# fc-comms.net
KiCad netlist of a schematic drawn in EAGLE
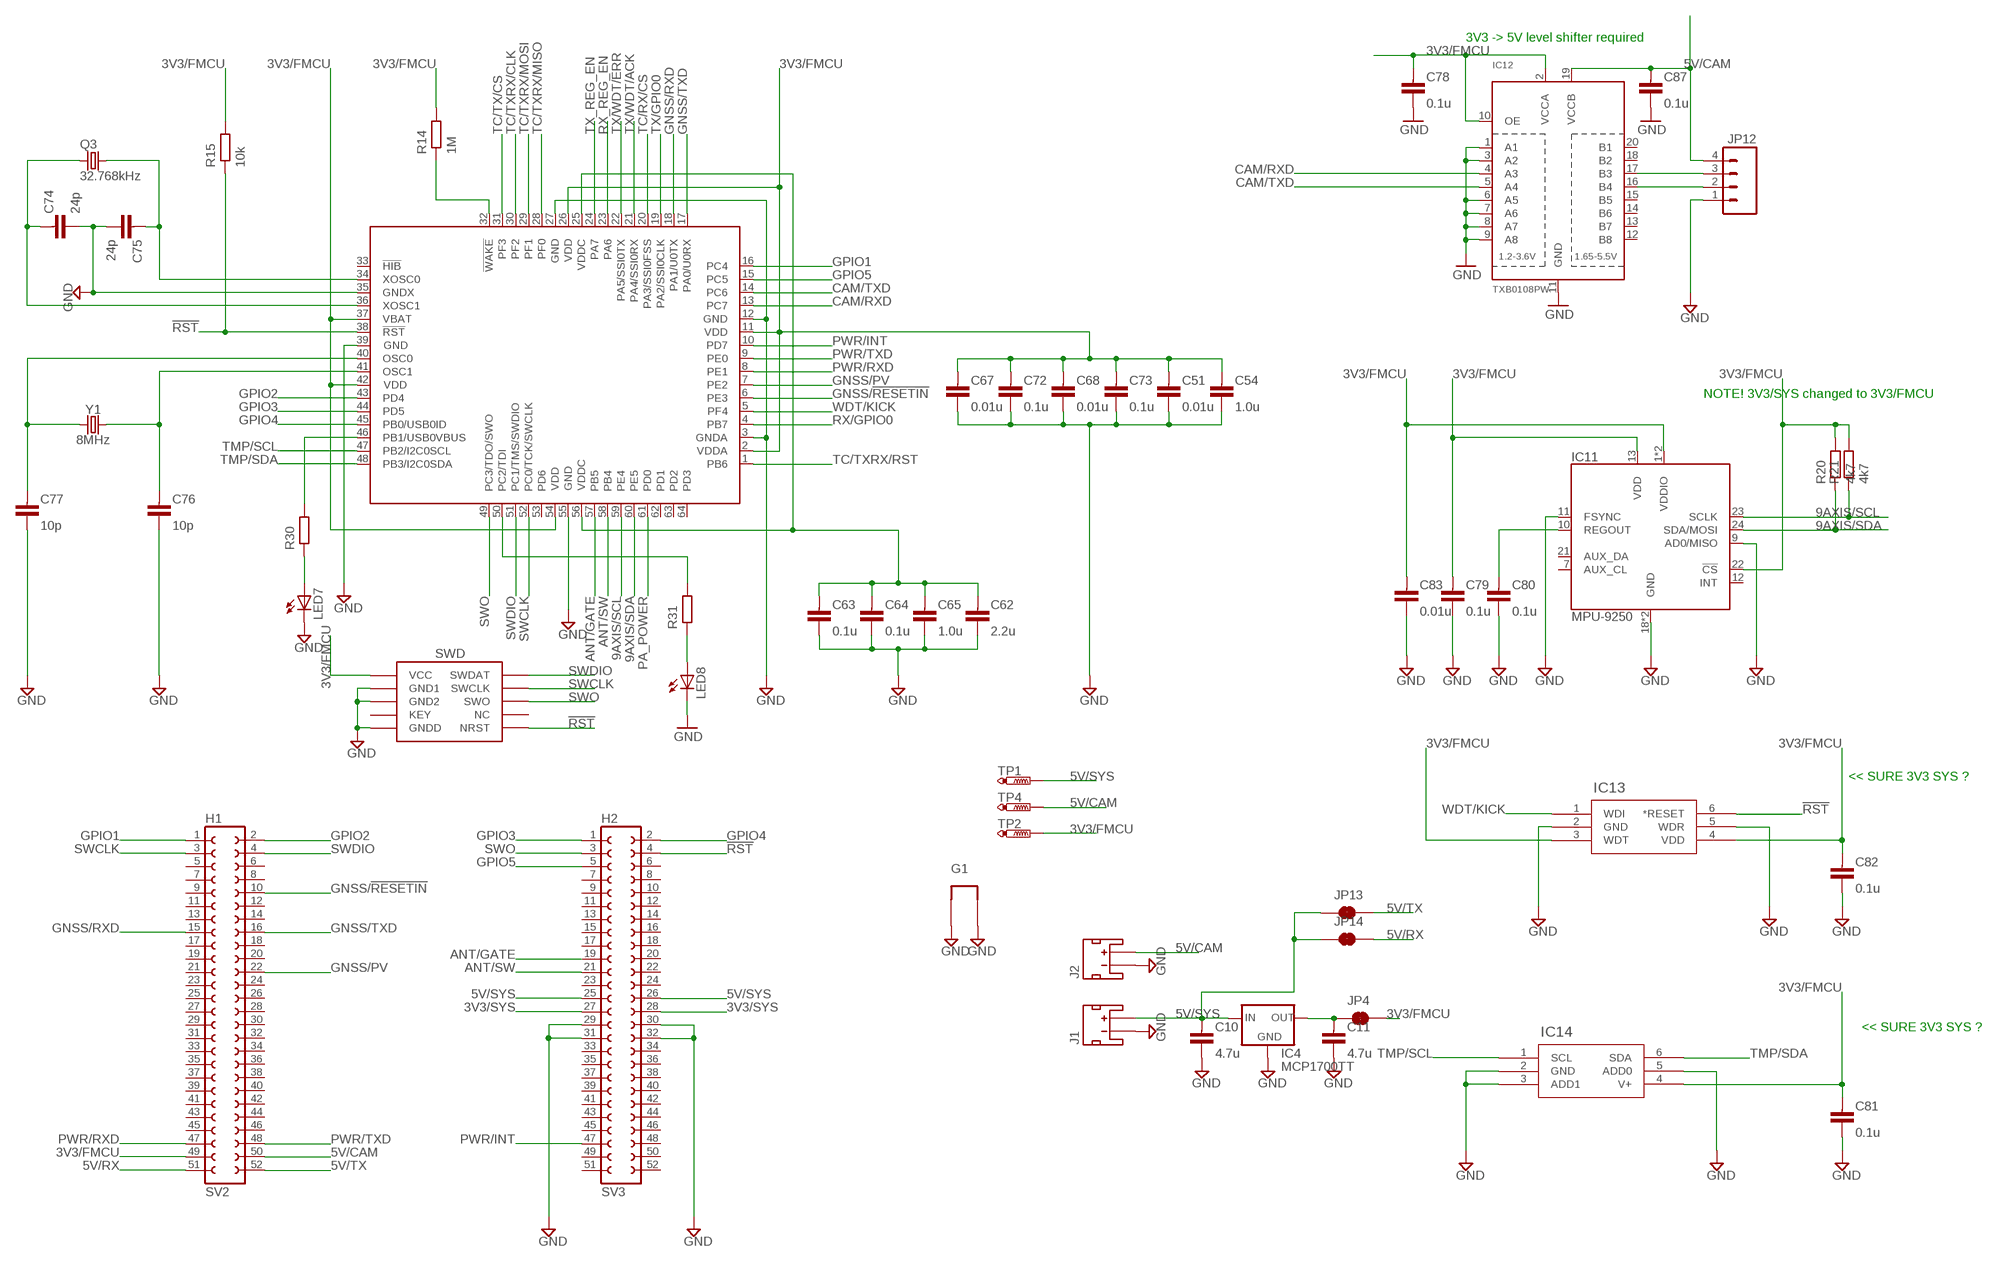
[diagram p0: schematic, sheet 1]
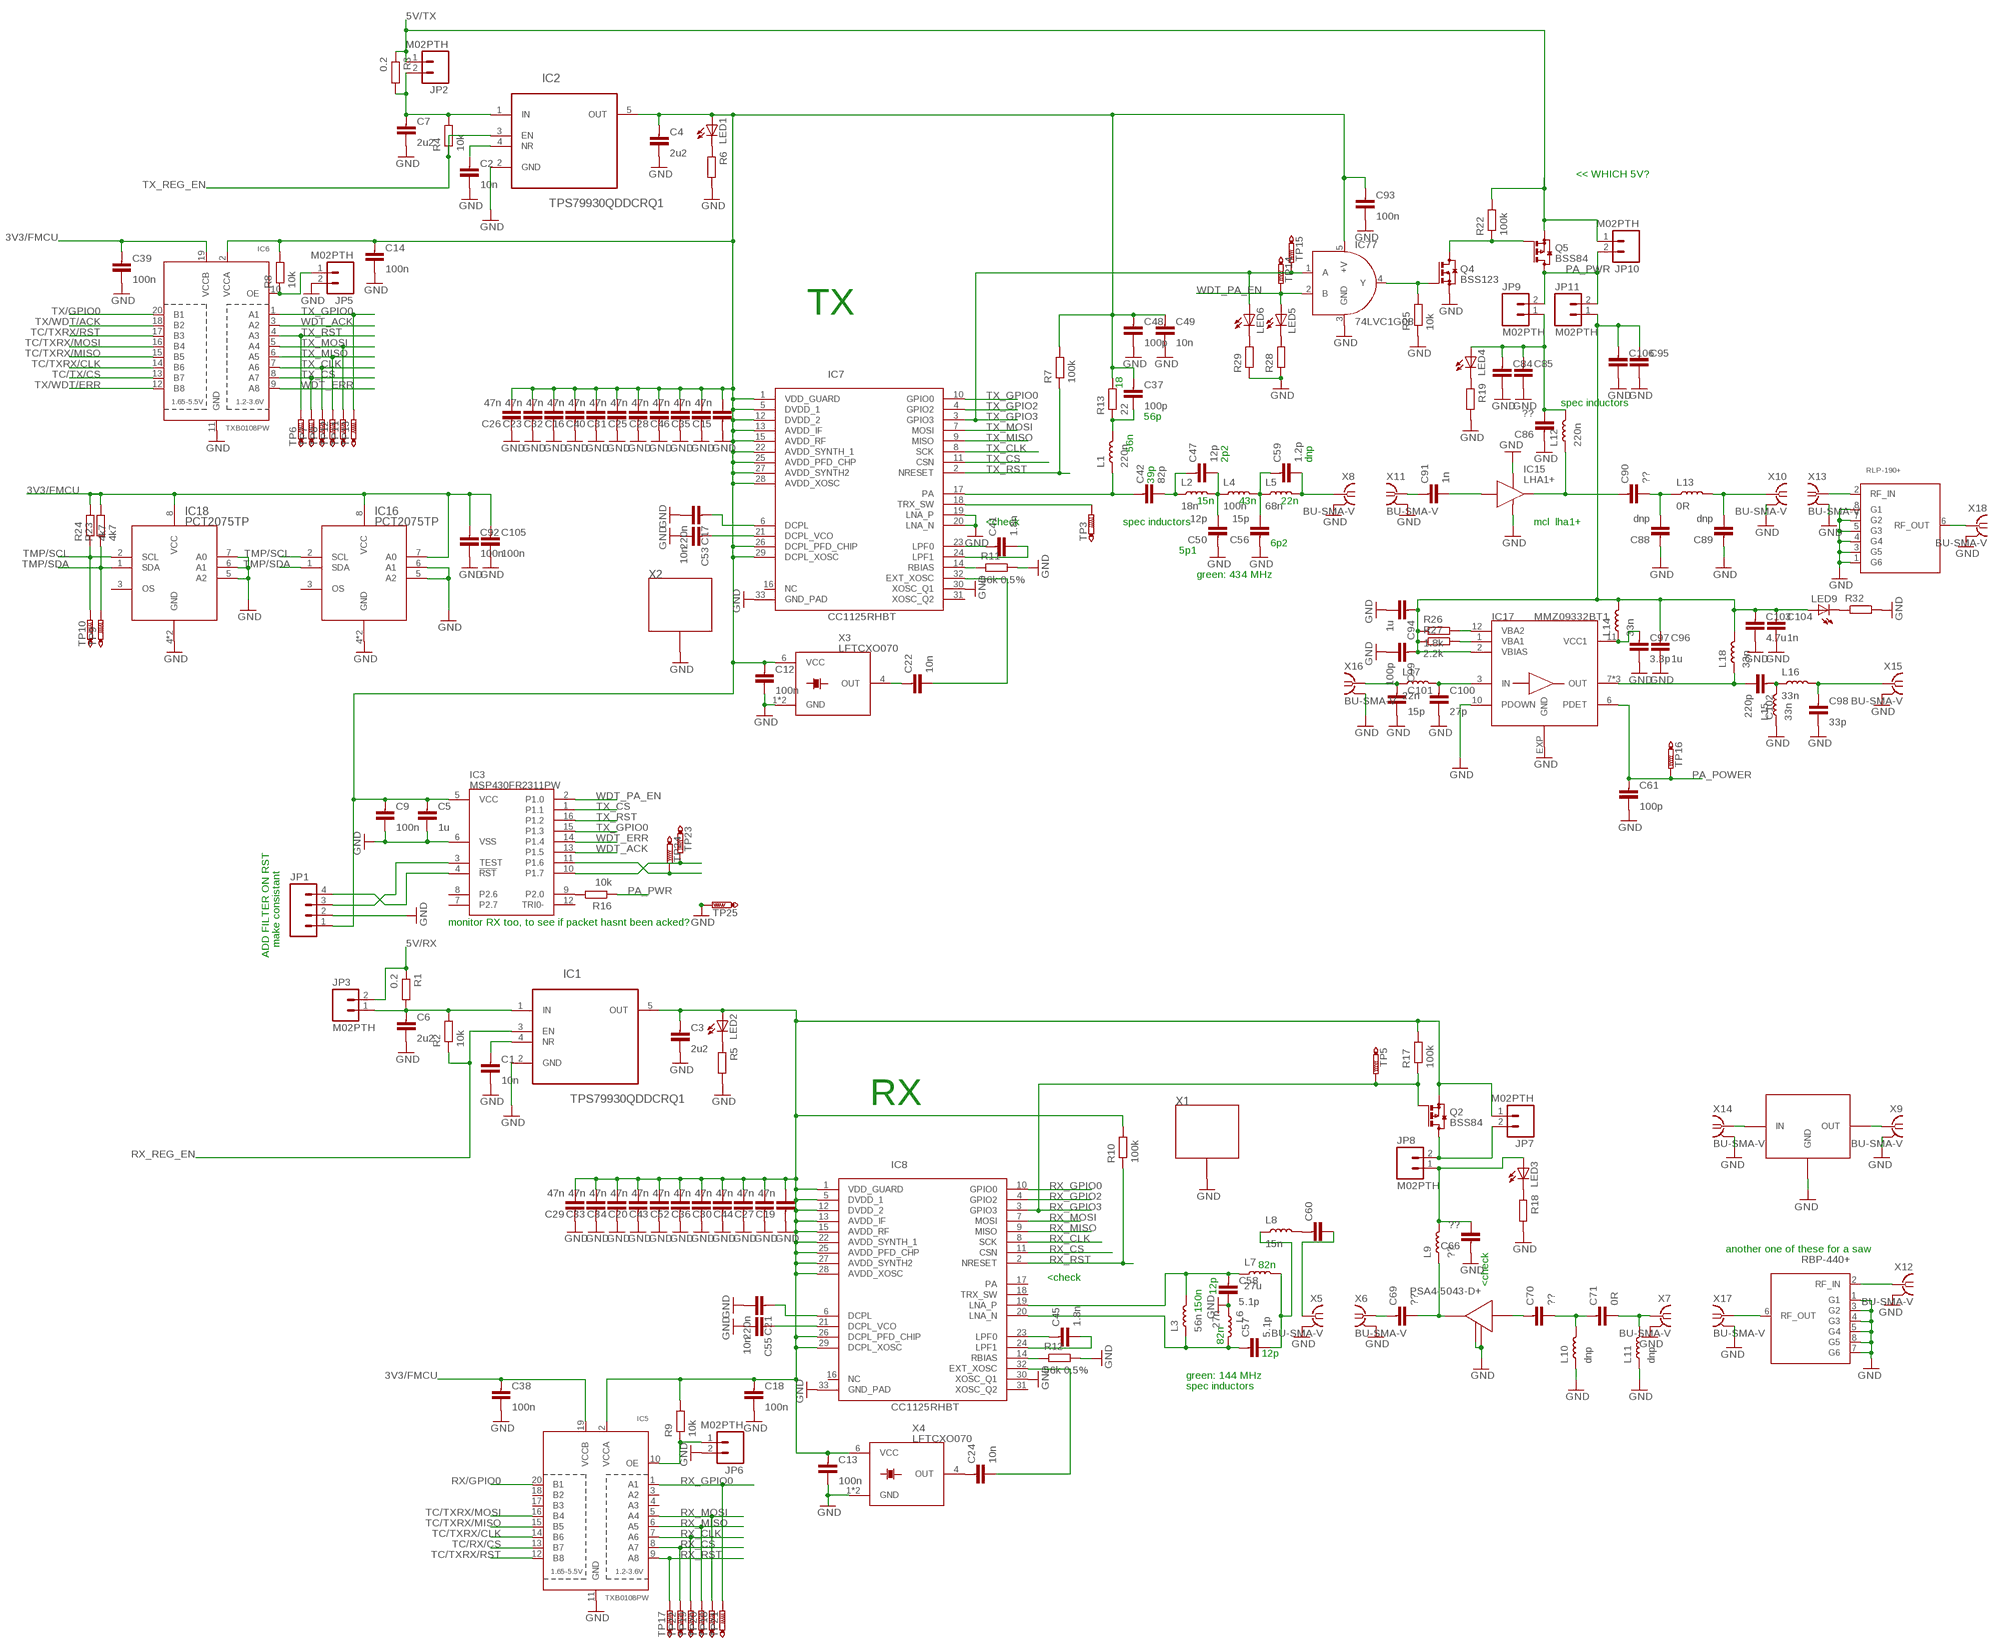
[diagram p1: schematic, sheet 2]

(export (version "E")
  (design (tool "Eeschema 10.0.6"))
  (components
    (comp (ref "C10")
      (value "4.7u")
      (footprint "eagle-import:C0603-N")
      (libsource (lib "eagle-import") (part "CAPACITOR0603-N"))
    )
    (comp (ref "C11")
      (value "4.7u")
      (footprint "eagle-import:C0603-N")
      (libsource (lib "eagle-import") (part "CAPACITOR0603-N"))
    )
    (comp (ref "C51")
      (value "0.01u")
      (footprint "eagle-import:C0603-N")
      (libsource (lib "eagle-import") (part "CAPACITOR0603-N"))
    )
    (comp (ref "C54")
      (value "1.0u")
      (footprint "eagle-import:C0603-N")
      (libsource (lib "eagle-import") (part "CAPACITOR0603-N"))
    )
    (comp (ref "C62")
      (value "2.2u")
      (footprint "eagle-import:C0603-N")
      (libsource (lib "eagle-import") (part "CAPACITOR0603-N"))
    )
    (comp (ref "C63")
      (value "0.1u")
      (footprint "eagle-import:C0603-N")
      (libsource (lib "eagle-import") (part "CAPACITOR0603-N"))
    )
    (comp (ref "C64")
      (value "0.1u")
      (footprint "eagle-import:C0603-N")
      (libsource (lib "eagle-import") (part "CAPACITOR0603-N"))
    )
    (comp (ref "C65")
      (value "1.0u")
      (footprint "eagle-import:C0603-N")
      (libsource (lib "eagle-import") (part "CAPACITOR0603-N"))
    )
    (comp (ref "C67")
      (value "0.01u")
      (footprint "eagle-import:C0603-N")
      (libsource (lib "eagle-import") (part "CAPACITOR0603-N"))
    )
    (comp (ref "C68")
      (value "0.01u")
      (footprint "eagle-import:C0603-N")
      (libsource (lib "eagle-import") (part "CAPACITOR0603-N"))
    )
    (comp (ref "C72")
      (value "0.1u")
      (footprint "eagle-import:C0603-N")
      (libsource (lib "eagle-import") (part "CAPACITOR0603-N"))
    )
    (comp (ref "C73")
      (value "0.1u")
      (footprint "eagle-import:C0603-N")
      (libsource (lib "eagle-import") (part "CAPACITOR0603-N"))
    )
    (comp (ref "C74")
      (value "24p")
      (footprint "eagle-import:C0603-N")
      (libsource (lib "eagle-import") (part "CAPACITOR0603-N"))
    )
    (comp (ref "C75")
      (value "24p")
      (footprint "eagle-import:C0603-N")
      (libsource (lib "eagle-import") (part "CAPACITOR0603-N"))
    )
    (comp (ref "C76")
      (value "10p")
      (footprint "eagle-import:C0603-N")
      (libsource (lib "eagle-import") (part "CAPACITOR0603-N"))
    )
    (comp (ref "C77")
      (value "10p")
      (footprint "eagle-import:C0603-N")
      (libsource (lib "eagle-import") (part "CAPACITOR0603-N"))
    )
    (comp (ref "C78")
      (value "0.1u")
      (footprint "eagle-import:C0603-N")
      (libsource (lib "eagle-import") (part "CAPACITOR0603-N"))
    )
    (comp (ref "C79")
      (value "0.1u")
      (footprint "eagle-import:C0603-N")
      (libsource (lib "eagle-import") (part "CAPACITOR0603-N"))
    )
    (comp (ref "C80")
      (value "0.1u")
      (footprint "eagle-import:C0603-N")
      (libsource (lib "eagle-import") (part "CAPACITOR0603-N"))
    )
    (comp (ref "C81")
      (value "0.1u")
      (footprint "eagle-import:C0603-N")
      (libsource (lib "eagle-import") (part "CAPACITOR0603-N"))
    )
    (comp (ref "C82")
      (value "0.1u")
      (footprint "eagle-import:C0603-N")
      (libsource (lib "eagle-import") (part "CAPACITOR0603-N"))
    )
    (comp (ref "C83")
      (value "0.01u")
      (footprint "eagle-import:C0603-N")
      (libsource (lib "eagle-import") (part "CAPACITOR0603-N"))
    )
    (comp (ref "C87")
      (value "0.1u")
      (footprint "eagle-import:C0603-N")
      (libsource (lib "eagle-import") (part "CAPACITOR0603-N"))
    )
    (comp (ref "G1")
      (value "GND-LOOPL")
      (footprint "eagle-import:GND-LOOP-0.4")
      (libsource (lib "eagle-import") (part "GND-LOOPL"))
    )
    (comp (ref "IC4")
      (value "MCP1700TT")
      (footprint "eagle-import:SOT23")
      (libsource (lib "eagle-import") (part "MCP1700TT"))
    )
    (comp (ref "IC9")
      (value "TM4C123[7,G]XXPM")
      (footprint "eagle-import:PM_S-PQFP-G64")
      (libsource (lib "eagle-import") (part "TM4C123[7,G]XXPM"))
    )
    (comp (ref "IC11")
      (value "MPU-9250")
      (footprint "eagle-import:QFN-24_3MM")
      (libsource (lib "eagle-import") (part "MPU-9250"))
    )
    (comp (ref "IC12")
      (value "TXB0108PW")
      (footprint "eagle-import:TSSOP20")
      (libsource (lib "eagle-import") (part "TXB0108PW"))
    )
    (comp (ref "IC13")
      (value "TPS3813K33-EP_DBV_6")
      (footprint "eagle-import:DBV6")
      (fields
        (field (name "GENERIC_PART_NUMBER") "TPS3813K33-EP")
        (field (name "MANUFACTURER") "Texas Instruments")
        (field (name "MANUFACTURER_PART_NUMBER") "tps3813k33-ep_dbv_6")
      )
      (libsource (lib "eagle-import") (part "TPS3813K33-EP_DBV_6"))
    )
    (comp (ref "IC14")
      (value "TMP100-EP_DBV_6")
      (footprint "eagle-import:DBV6")
      (fields
        (field (name "GENERIC_PART_NUMBER") "TMP100-EP")
        (field (name "MANUFACTURER") "Texas Instruments")
        (field (name "MANUFACTURER_PART_NUMBER") "tmp100-ep_dbv_6")
      )
      (libsource (lib "eagle-import") (part "TMP100-EP_DBV_6"))
    )
    (comp (ref "J1")
      (value "JST_2MM_MALE_TH")
      (footprint "eagle-import:JST-2-TH")
      (libsource (lib "eagle-import") (part "JST_2MM_MALE_TH"))
    )
    (comp (ref "J2")
      (value "JST_2MM_MALE_TH")
      (footprint "eagle-import:JST-2-TH")
      (libsource (lib "eagle-import") (part "JST_2MM_MALE_TH"))
    )
    (comp (ref "J3")
      (value "SWD_SHROUD")
      (footprint "eagle-import:SWD_PTH_SHROUD")
      (libsource (lib "eagle-import") (part "SWD_SHROUD"))
    )
    (comp (ref "JP4")
      (value "JUMPER-SMT_2_NC_TRACE_SILK")
      (footprint "eagle-import:SMT-JUMPER_2_NC_TRACE_SILK")
      (libsource (lib "eagle-import") (part "JUMPER-SMT_2_NC_TRACE_SILK"))
    )
    (comp (ref "JP12")
      (value "M04PTH")
      (footprint "eagle-import:1X04")
      (libsource (lib "eagle-import") (part "M04PTH"))
    )
    (comp (ref "JP13")
      (value "JUMPER-SMT_2_NC_TRACE_SILK")
      (footprint "eagle-import:SMT-JUMPER_2_NC_TRACE_SILK")
      (libsource (lib "eagle-import") (part "JUMPER-SMT_2_NC_TRACE_SILK"))
    )
    (comp (ref "JP14")
      (value "JUMPER-SMT_2_NC_TRACE_SILK")
      (footprint "eagle-import:SMT-JUMPER_2_NC_TRACE_SILK")
      (libsource (lib "eagle-import") (part "JUMPER-SMT_2_NC_TRACE_SILK"))
    )
    (comp (ref "LED7")
      (value "LEDCHIP-LED0603")
      (footprint "eagle-import:CHIP-LED0603")
      (libsource (lib "eagle-import") (part "LEDCHIP-LED0603"))
    )
    (comp (ref "LED8")
      (value "LEDCHIP-LED0603")
      (footprint "eagle-import:CHIP-LED0603")
      (libsource (lib "eagle-import") (part "LEDCHIP-LED0603"))
    )
    (comp (ref "Q3")
      (value "32.768kHz")
      (footprint "eagle-import:RESONATOR_EPSON_FC_145")
      (libsource (lib "eagle-import") (part "RESONATOR_EPSON_FC_145"))
    )
    (comp (ref "R14")
      (value "1M")
      (footprint "eagle-import:R0603-N")
      (libsource (lib "eagle-import") (part "RESISTOR0603-N"))
    )
    (comp (ref "R15")
      (value "10k")
      (footprint "eagle-import:R0603-N")
      (libsource (lib "eagle-import") (part "RESISTOR0603-N"))
    )
    (comp (ref "R20")
      (value "4k7")
      (footprint "eagle-import:R0603-N")
      (libsource (lib "eagle-import") (part "RESISTOR0603-N"))
    )
    (comp (ref "R21")
      (value "4k7")
      (footprint "eagle-import:R0603-N")
      (libsource (lib "eagle-import") (part "RESISTOR0603-N"))
    )
    (comp (ref "R30")
      (value "RESISTOR0603-N")
      (footprint "eagle-import:R0603-N")
      (libsource (lib "eagle-import") (part "RESISTOR0603-N"))
    )
    (comp (ref "R31")
      (value "RESISTOR0603-N")
      (footprint "eagle-import:R0603-N")
      (libsource (lib "eagle-import") (part "RESISTOR0603-N"))
    )
    (comp (ref "SV2")
      (value "H1")
      (footprint "eagle-import:FE26-2")
      (libsource (lib "eagle-import") (part "FE26-2"))
    )
    (comp (ref "SV3")
      (value "H2")
      (footprint "eagle-import:FE26-2")
      (libsource (lib "eagle-import") (part "FE26-2"))
    )
    (comp (ref "TP1")
      (value "PTR1PAD1-13")
      (footprint "eagle-import:P1-13")
      (libsource (lib "eagle-import") (part "PTR1PAD1-13"))
    )
    (comp (ref "TP2")
      (value "PTR1PAD1-13")
      (footprint "eagle-import:P1-13")
      (libsource (lib "eagle-import") (part "PTR1PAD1-13"))
    )
    (comp (ref "TP4")
      (value "PTR1PAD1-13")
      (footprint "eagle-import:P1-13")
      (libsource (lib "eagle-import") (part "PTR1PAD1-13"))
    )
    (comp (ref "Y1")
      (value "8MHz")
      (footprint "eagle-import:CRYSTAL-SMD-5X3.2-4PAD")
      (libsource (lib "eagle-import") (part "CRYSTAL-8MHZSMD-5X3.2"))
    )
    (comp (ref "C1")
      (value "10n")
      (footprint "eagle-import:C0603-N")
      (libsource (lib "eagle-import") (part "CAPACITOR0603-N"))
    )
    (comp (ref "C2")
      (value "10n")
      (footprint "eagle-import:C0603-N")
      (libsource (lib "eagle-import") (part "CAPACITOR0603-N"))
    )
    (comp (ref "C3")
      (value "2u2")
      (footprint "eagle-import:C0603-N")
      (libsource (lib "eagle-import") (part "CAPACITOR0603-N"))
    )
    (comp (ref "C4")
      (value "2u2")
      (footprint "eagle-import:C0603-N")
      (libsource (lib "eagle-import") (part "CAPACITOR0603-N"))
    )
    (comp (ref "C5")
      (value "1u")
      (footprint "eagle-import:C0603-N")
      (libsource (lib "eagle-import") (part "CAPACITOR0603-N"))
    )
    (comp (ref "C6")
      (value "2u2")
      (footprint "eagle-import:C0603-N")
      (libsource (lib "eagle-import") (part "CAPACITOR0603-N"))
    )
    (comp (ref "C7")
      (value "2u2")
      (footprint "eagle-import:C0603-N")
      (libsource (lib "eagle-import") (part "CAPACITOR0603-N"))
    )
    (comp (ref "C9")
      (value "100n")
      (footprint "eagle-import:C0603-N")
      (libsource (lib "eagle-import") (part "CAPACITOR0603-N"))
    )
    (comp (ref "C12")
      (value "100n")
      (footprint "eagle-import:C0603-N")
      (libsource (lib "eagle-import") (part "CAPACITOR0603-N"))
    )
    (comp (ref "C13")
      (value "100n")
      (footprint "eagle-import:C0603-N")
      (libsource (lib "eagle-import") (part "CAPACITOR0603-N"))
    )
    (comp (ref "C14")
      (value "100n")
      (footprint "eagle-import:C0603-N")
      (libsource (lib "eagle-import") (part "CAPACITOR0603-N"))
    )
    (comp (ref "C15")
      (value "47n")
      (footprint "eagle-import:C0603-N")
      (libsource (lib "eagle-import") (part "CAPACITOR0603-N"))
    )
    (comp (ref "C16")
      (value "47n")
      (footprint "eagle-import:C0603-N")
      (libsource (lib "eagle-import") (part "CAPACITOR0603-N"))
    )
    (comp (ref "C17")
      (value "220n")
      (footprint "eagle-import:C0603-N")
      (libsource (lib "eagle-import") (part "CAPACITOR0603-N"))
    )
    (comp (ref "C18")
      (value "100n")
      (footprint "eagle-import:C0603-N")
      (libsource (lib "eagle-import") (part "CAPACITOR0603-N"))
    )
    (comp (ref "C19")
      (value "47n")
      (footprint "eagle-import:C0603-N")
      (libsource (lib "eagle-import") (part "CAPACITOR0603-N"))
    )
    (comp (ref "C20")
      (value "47n")
      (footprint "eagle-import:C0603-N")
      (libsource (lib "eagle-import") (part "CAPACITOR0603-N"))
    )
    (comp (ref "C21")
      (value "220n")
      (footprint "eagle-import:C0603-N")
      (libsource (lib "eagle-import") (part "CAPACITOR0603-N"))
    )
    (comp (ref "C22")
      (value "10n")
      (footprint "eagle-import:C0603-N")
      (libsource (lib "eagle-import") (part "CAPACITOR0603-N"))
    )
    (comp (ref "C23")
      (value "47n")
      (footprint "eagle-import:C0603-N")
      (libsource (lib "eagle-import") (part "CAPACITOR0603-N"))
    )
    (comp (ref "C24")
      (value "10n")
      (footprint "eagle-import:C0603-N")
      (libsource (lib "eagle-import") (part "CAPACITOR0603-N"))
    )
    (comp (ref "C25")
      (value "47n")
      (footprint "eagle-import:C0603-N")
      (libsource (lib "eagle-import") (part "CAPACITOR0603-N"))
    )
    (comp (ref "C26")
      (value "47n")
      (footprint "eagle-import:C0603-N")
      (libsource (lib "eagle-import") (part "CAPACITOR0603-N"))
    )
    (comp (ref "C27")
      (value "47n")
      (footprint "eagle-import:C0603-N")
      (libsource (lib "eagle-import") (part "CAPACITOR0603-N"))
    )
    (comp (ref "C28")
      (value "47n")
      (footprint "eagle-import:C0603-N")
      (libsource (lib "eagle-import") (part "CAPACITOR0603-N"))
    )
    (comp (ref "C29")
      (value "47n")
      (footprint "eagle-import:C0603-N")
      (libsource (lib "eagle-import") (part "CAPACITOR0603-N"))
    )
    (comp (ref "C30")
      (value "47n")
      (footprint "eagle-import:C0603-N")
      (libsource (lib "eagle-import") (part "CAPACITOR0603-N"))
    )
    (comp (ref "C31")
      (value "47n")
      (footprint "eagle-import:C0603-N")
      (libsource (lib "eagle-import") (part "CAPACITOR0603-N"))
    )
    (comp (ref "C32")
      (value "47n")
      (footprint "eagle-import:C0603-N")
      (libsource (lib "eagle-import") (part "CAPACITOR0603-N"))
    )
    (comp (ref "C33")
      (value "47n")
      (footprint "eagle-import:C0603-N")
      (libsource (lib "eagle-import") (part "CAPACITOR0603-N"))
    )
    (comp (ref "C34")
      (value "47n")
      (footprint "eagle-import:C0603-N")
      (libsource (lib "eagle-import") (part "CAPACITOR0603-N"))
    )
    (comp (ref "C35")
      (value "47n")
      (footprint "eagle-import:C0603-N")
      (libsource (lib "eagle-import") (part "CAPACITOR0603-N"))
    )
    (comp (ref "C36")
      (value "47n")
      (footprint "eagle-import:C0603-N")
      (libsource (lib "eagle-import") (part "CAPACITOR0603-N"))
    )
    (comp (ref "C37")
      (value "100p")
      (footprint "eagle-import:C0603-N")
      (libsource (lib "eagle-import") (part "CAPACITOR0603-N"))
    )
    (comp (ref "C38")
      (value "100n")
      (footprint "eagle-import:C0603-N")
      (libsource (lib "eagle-import") (part "CAPACITOR0603-N"))
    )
    (comp (ref "C39")
      (value "100n")
      (footprint "eagle-import:C0603-N")
      (libsource (lib "eagle-import") (part "CAPACITOR0603-N"))
    )
    (comp (ref "C40")
      (value "47n")
      (footprint "eagle-import:C0603-N")
      (libsource (lib "eagle-import") (part "CAPACITOR0603-N"))
    )
    (comp (ref "C41")
      (value "1.8n")
      (footprint "eagle-import:C0603-N")
      (libsource (lib "eagle-import") (part "CAPACITOR0603-N"))
    )
    (comp (ref "C42")
      (value "82p")
      (footprint "eagle-import:C0603-N")
      (libsource (lib "eagle-import") (part "CAPACITOR0603-N"))
    )
    (comp (ref "C43")
      (value "47n")
      (footprint "eagle-import:C0603-N")
      (libsource (lib "eagle-import") (part "CAPACITOR0603-N"))
    )
    (comp (ref "C44")
      (value "47n")
      (footprint "eagle-import:C0603-N")
      (libsource (lib "eagle-import") (part "CAPACITOR0603-N"))
    )
    (comp (ref "C45")
      (value "1.8n")
      (footprint "eagle-import:C0603-N")
      (libsource (lib "eagle-import") (part "CAPACITOR0603-N"))
    )
    (comp (ref "C46")
      (value "47n")
      (footprint "eagle-import:C0603-N")
      (libsource (lib "eagle-import") (part "CAPACITOR0603-N"))
    )
    (comp (ref "C47")
      (value "12p")
      (footprint "eagle-import:C0603-N")
      (libsource (lib "eagle-import") (part "CAPACITOR0603-N"))
    )
    (comp (ref "C48")
      (value "100p")
      (footprint "eagle-import:C0603-N")
      (libsource (lib "eagle-import") (part "CAPACITOR0603-N"))
    )
    (comp (ref "C49")
      (value "10n")
      (footprint "eagle-import:C0603-N")
      (libsource (lib "eagle-import") (part "CAPACITOR0603-N"))
    )
    (comp (ref "C50")
      (value "12p")
      (footprint "eagle-import:C0603-N")
      (libsource (lib "eagle-import") (part "CAPACITOR0603-N"))
    )
    (comp (ref "C52")
      (value "47n")
      (footprint "eagle-import:C0603-N")
      (libsource (lib "eagle-import") (part "CAPACITOR0603-N"))
    )
    (comp (ref "C53")
      (value "10n")
      (footprint "eagle-import:C0603-N")
      (libsource (lib "eagle-import") (part "CAPACITOR0603-N"))
    )
    (comp (ref "C55")
      (value "10n")
      (footprint "eagle-import:C0603-N")
      (libsource (lib "eagle-import") (part "CAPACITOR0603-N"))
    )
    (comp (ref "C56")
      (value "15p")
      (footprint "eagle-import:C0603-N")
      (libsource (lib "eagle-import") (part "CAPACITOR0603-N"))
    )
    (comp (ref "C57")
      (value "5.1p")
      (footprint "eagle-import:C0603-N")
      (libsource (lib "eagle-import") (part "CAPACITOR0603-N"))
    )
    (comp (ref "C58")
      (value "5.1p")
      (footprint "eagle-import:C0603-N")
      (libsource (lib "eagle-import") (part "CAPACITOR0603-N"))
    )
    (comp (ref "C59")
      (value "1.2p")
      (footprint "eagle-import:C0603-N")
      (libsource (lib "eagle-import") (part "CAPACITOR0603-N"))
    )
    (comp (ref "C60")
      (value "CAPACITOR0603-N")
      (footprint "eagle-import:C0603-N")
      (libsource (lib "eagle-import") (part "CAPACITOR0603-N"))
    )
    (comp (ref "C61")
      (value "100p")
      (footprint "eagle-import:C0603-N")
      (libsource (lib "eagle-import") (part "CAPACITOR0603-N"))
    )
    (comp (ref "C66")
      (value "??")
      (footprint "eagle-import:C0603-N")
      (libsource (lib "eagle-import") (part "CAPACITOR0603-N"))
    )
    (comp (ref "C69")
      (value "??")
      (footprint "eagle-import:C0603-N")
      (libsource (lib "eagle-import") (part "CAPACITOR0603-N"))
    )
    (comp (ref "C70")
      (value "??")
      (footprint "eagle-import:C0603-N")
      (libsource (lib "eagle-import") (part "CAPACITOR0603-N"))
    )
    (comp (ref "C71")
      (value "0R")
      (footprint "eagle-import:C0603-N")
      (libsource (lib "eagle-import") (part "CAPACITOR0603-N"))
    )
    (comp (ref "C84")
      (value "CAPACITOR0805-N")
      (footprint "eagle-import:C0805-N")
      (libsource (lib "eagle-import") (part "CAPACITOR0805-N"))
    )
    (comp (ref "C85")
      (value "CAPACITOR0805-N")
      (footprint "eagle-import:C0805-N")
      (libsource (lib "eagle-import") (part "CAPACITOR0805-N"))
    )
    (comp (ref "C86")
      (value "??")
      (footprint "eagle-import:C0603-N")
      (libsource (lib "eagle-import") (part "CAPACITOR0603-N"))
    )
    (comp (ref "C88")
      (value "dnp")
      (footprint "eagle-import:C0603-N")
      (libsource (lib "eagle-import") (part "CAPACITOR0603-N"))
    )
    (comp (ref "C89")
      (value "dnp")
      (footprint "eagle-import:C0603-N")
      (libsource (lib "eagle-import") (part "CAPACITOR0603-N"))
    )
    (comp (ref "C90")
      (value "??")
      (footprint "eagle-import:C0603-N")
      (libsource (lib "eagle-import") (part "CAPACITOR0603-N"))
    )
    (comp (ref "C91")
      (value "1n")
      (footprint "eagle-import:C0603-N")
      (libsource (lib "eagle-import") (part "CAPACITOR0603-N"))
    )
    (comp (ref "C92")
      (value "100n")
      (footprint "eagle-import:C0603-N")
      (libsource (lib "eagle-import") (part "CAPACITOR0603-N"))
    )
    (comp (ref "C93")
      (value "100n")
      (footprint "eagle-import:C0603-N")
      (libsource (lib "eagle-import") (part "CAPACITOR0603-N"))
    )
    (comp (ref "C94")
      (value "1u")
      (footprint "eagle-import:C0603-N")
      (libsource (lib "eagle-import") (part "CAPACITOR0603-N"))
    )
    (comp (ref "C95")
      (value "CAPACITOR0805-N")
      (footprint "eagle-import:C0805-N")
      (libsource (lib "eagle-import") (part "CAPACITOR0805-N"))
    )
    (comp (ref "C96")
      (value "1u")
      (footprint "eagle-import:C0603-N")
      (libsource (lib "eagle-import") (part "CAPACITOR0603-N"))
    )
    (comp (ref "C97")
      (value "3.3p")
      (footprint "eagle-import:C0603-N")
      (libsource (lib "eagle-import") (part "CAPACITOR0603-N"))
    )
    (comp (ref "C98")
      (value "33p")
      (footprint "eagle-import:C0603-N")
      (libsource (lib "eagle-import") (part "CAPACITOR0603-N"))
    )
    (comp (ref "C99")
      (value "100p")
      (footprint "eagle-import:C0603-N")
      (libsource (lib "eagle-import") (part "CAPACITOR0603-N"))
    )
    (comp (ref "C100")
      (value "27p")
      (footprint "eagle-import:C0603-N")
      (libsource (lib "eagle-import") (part "CAPACITOR0603-N"))
    )
    (comp (ref "C101")
      (value "15p")
      (footprint "eagle-import:C0603-N")
      (libsource (lib "eagle-import") (part "CAPACITOR0603-N"))
    )
    (comp (ref "C102")
      (value "220p")
      (footprint "eagle-import:C0603-N")
      (libsource (lib "eagle-import") (part "CAPACITOR0603-N"))
    )
    (comp (ref "C103")
      (value "4.7u")
      (footprint "eagle-import:C0603-N")
      (libsource (lib "eagle-import") (part "CAPACITOR0603-N"))
    )
    (comp (ref "C104")
      (value "1n")
      (footprint "eagle-import:C0603-N")
      (libsource (lib "eagle-import") (part "CAPACITOR0603-N"))
    )
    (comp (ref "C105")
      (value "100n")
      (footprint "eagle-import:C0603-N")
      (libsource (lib "eagle-import") (part "CAPACITOR0603-N"))
    )
    (comp (ref "C106")
      (value "CAPACITOR0805-N")
      (footprint "eagle-import:C0805-N")
      (libsource (lib "eagle-import") (part "CAPACITOR0805-N"))
    )
    (comp (ref "FL1")
      (value "GOLLEDGE_SAW_FILTER")
      (footprint "eagle-import:GOLLEDGE_SAW")
      (libsource (lib "eagle-import") (part "GOLLEDGE_SAW_FILTER"))
    )
    (comp (ref "FL2")
      (value "SAW_FILTER_CS")
      (footprint "eagle-import:PL-176")
      (libsource (lib "eagle-import") (part "SAW_FILTER_CS"))
    )
    (comp (ref "FL3")
      (value "LPF_CS")
      (footprint "eagle-import:PL-176")
      (libsource (lib "eagle-import") (part "LPF_CS"))
    )
    (comp (ref "IC1")
      (value "TPS79930QDDCRQ1")
      (footprint "eagle-import:SOT95P280X110-5N")
      (fields (field (name "MPN") "TPS79933QDDCRQ1"))
      (libsource (lib "eagle-import") (part "TPS79933QDDCRQ1"))
    )
    (comp (ref "IC2")
      (value "TPS79930QDDCRQ1")
      (footprint "eagle-import:SOT95P280X110-5N")
      (fields (field (name "MPN") "TPS79933QDDCRQ1"))
      (libsource (lib "eagle-import") (part "TPS79933QDDCRQ1"))
    )
    (comp (ref "IC3")
      (value "MSP430FR2311PW")
      (footprint "eagle-import:SSOP16")
      (libsource (lib "eagle-import") (part "MSP430FR2311PW"))
    )
    (comp (ref "IC5")
      (value "TXB0108PW")
      (footprint "eagle-import:TSSOP20")
      (libsource (lib "eagle-import") (part "TXB0108PW"))
    )
    (comp (ref "IC6")
      (value "TXB0108PW")
      (footprint "eagle-import:TSSOP20")
      (libsource (lib "eagle-import") (part "TXB0108PW"))
    )
    (comp (ref "IC7")
      (value "CC1125RHBT")
      (footprint "eagle-import:QFN32_5X5")
      (libsource (lib "eagle-import") (part "CC1125RHBT"))
    )
    (comp (ref "IC8")
      (value "CC1125RHBT")
      (footprint "eagle-import:QFN32_5X5")
      (libsource (lib "eagle-import") (part "CC1125RHBT"))
    )
    (comp (ref "IC10")
      (value "LNA_COMMON")
      (footprint "eagle-import:LNA_MMM1362")
      (libsource (lib "eagle-import") (part "LNA_COMMON"))
    )
    (comp (ref "IC15")
      (value "LHA1+")
      (footprint "eagle-import:PA")
      (libsource (lib "eagle-import") (part "PA"))
    )
    (comp (ref "IC16")
      (value "PCT2075TP")
      (footprint "eagle-import:HWSON8")
      (libsource (lib "eagle-import") (part "PCT2075TP"))
    )
    (comp (ref "IC17")
      (value "MMZ09332BT1")
      (footprint "eagle-import:QFN3X3-6")
      (libsource (lib "eagle-import") (part "MMZ09332BT1"))
    )
    (comp (ref "IC18")
      (value "PCT2075TP")
      (footprint "eagle-import:HWSON8")
      (libsource (lib "eagle-import") (part "PCT2075TP"))
    )
    (comp (ref "IC77")
      (value "74LVC1G08")
      (footprint "eagle-import:SOT23-5")
      (libsource (lib "eagle-import") (part "SN74LVC1G08"))
    )
    (comp (ref "JP1")
      (value "M04PTH")
      (footprint "eagle-import:1X04")
      (libsource (lib "eagle-import") (part "M04PTH"))
    )
    (comp (ref "JP2")
      (value "M02PTH")
      (footprint "eagle-import:1X02")
      (libsource (lib "eagle-import") (part "M02PTH"))
    )
    (comp (ref "JP3")
      (value "M02PTH")
      (footprint "eagle-import:1X02")
      (libsource (lib "eagle-import") (part "M02PTH"))
    )
    (comp (ref "JP5")
      (value "M02PTH")
      (footprint "eagle-import:1X02")
      (libsource (lib "eagle-import") (part "M02PTH"))
    )
    (comp (ref "JP6")
      (value "M02PTH")
      (footprint "eagle-import:1X02")
      (libsource (lib "eagle-import") (part "M02PTH"))
    )
    (comp (ref "JP7")
      (value "M02PTH")
      (footprint "eagle-import:1X02")
      (libsource (lib "eagle-import") (part "M02PTH"))
    )
    (comp (ref "JP8")
      (value "M02PTH")
      (footprint "eagle-import:1X02")
      (libsource (lib "eagle-import") (part "M02PTH"))
    )
    (comp (ref "JP9")
      (value "M02PTH")
      (footprint "eagle-import:1X02")
      (libsource (lib "eagle-import") (part "M02PTH"))
    )
    (comp (ref "JP10")
      (value "M02PTH")
      (footprint "eagle-import:1X02")
      (libsource (lib "eagle-import") (part "M02PTH"))
    )
    (comp (ref "JP11")
      (value "M02PTH")
      (footprint "eagle-import:1X02")
      (libsource (lib "eagle-import") (part "M02PTH"))
    )
    (comp (ref "L1")
      (value "220n")
      (footprint "eagle-import:L0603-N")
      (libsource (lib "eagle-import") (part "INDUCTOR0603-N"))
    )
    (comp (ref "L2")
      (value "18n")
      (footprint "eagle-import:L0603-N")
      (libsource (lib "eagle-import") (part "INDUCTOR0603-N"))
    )
    (comp (ref "L3")
      (value "56n")
      (footprint "eagle-import:L0603-N")
      (libsource (lib "eagle-import") (part "INDUCTOR0603-N"))
    )
    (comp (ref "L4")
      (value "100n")
      (footprint "eagle-import:L0603-N")
      (libsource (lib "eagle-import") (part "INDUCTOR0603-N"))
    )
    (comp (ref "L5")
      (value "68n")
      (footprint "eagle-import:L0603-N")
      (libsource (lib "eagle-import") (part "INDUCTOR0603-N"))
    )
    (comp (ref "L6")
      (value "27n")
      (footprint "eagle-import:L0603-N")
      (libsource (lib "eagle-import") (part "INDUCTOR0603-N"))
    )
    (comp (ref "L7")
      (value "27u")
      (footprint "eagle-import:L0603-N")
      (libsource (lib "eagle-import") (part "INDUCTOR0603-N"))
    )
    (comp (ref "L8")
      (value "15n")
      (footprint "eagle-import:L0603-N")
      (libsource (lib "eagle-import") (part "INDUCTOR0603-N"))
    )
    (comp (ref "L9")
      (value "??")
      (footprint "eagle-import:L0603-N")
      (libsource (lib "eagle-import") (part "INDUCTOR0603-N"))
    )
    (comp (ref "L10")
      (value "dnp")
      (footprint "eagle-import:L0603-N")
      (libsource (lib "eagle-import") (part "INDUCTOR0603-N"))
    )
    (comp (ref "L11")
      (value "dnp")
      (footprint "eagle-import:L0603-N")
      (libsource (lib "eagle-import") (part "INDUCTOR0603-N"))
    )
    (comp (ref "L12")
      (value "220n")
      (footprint "eagle-import:L0603-N")
      (libsource (lib "eagle-import") (part "INDUCTOR0603-N"))
    )
    (comp (ref "L13")
      (value "0R")
      (footprint "eagle-import:L0603-N")
      (libsource (lib "eagle-import") (part "INDUCTOR0603-N"))
    )
    (comp (ref "L14")
      (value "33n")
      (footprint "eagle-import:L0603-N")
      (libsource (lib "eagle-import") (part "INDUCTOR0603-N"))
    )
    (comp (ref "L15")
      (value "33n")
      (footprint "eagle-import:L0603-N")
      (libsource (lib "eagle-import") (part "INDUCTOR0603-N"))
    )
    (comp (ref "L16")
      (value "33n")
      (footprint "eagle-import:L0603-N")
      (libsource (lib "eagle-import") (part "INDUCTOR0603-N"))
    )
    (comp (ref "L17")
      (value "22n")
      (footprint "eagle-import:L0603-N")
      (libsource (lib "eagle-import") (part "INDUCTOR0603-N"))
    )
    (comp (ref "L18")
      (value "33n")
      (footprint "eagle-import:L0603-N")
      (libsource (lib "eagle-import") (part "INDUCTOR0603-N"))
    )
    (comp (ref "LED1")
      (value "LEDCHIP-LED0603")
      (footprint "eagle-import:CHIP-LED0603")
      (libsource (lib "eagle-import") (part "LEDCHIP-LED0603"))
    )
    (comp (ref "LED2")
      (value "LEDCHIP-LED0603")
      (footprint "eagle-import:CHIP-LED0603")
      (libsource (lib "eagle-import") (part "LEDCHIP-LED0603"))
    )
    (comp (ref "LED3")
      (value "LEDCHIP-LED0603")
      (footprint "eagle-import:CHIP-LED0603")
      (libsource (lib "eagle-import") (part "LEDCHIP-LED0603"))
    )
    (comp (ref "LED4")
      (value "LEDCHIP-LED0603")
      (footprint "eagle-import:CHIP-LED0603")
      (libsource (lib "eagle-import") (part "LEDCHIP-LED0603"))
    )
    (comp (ref "LED5")
      (value "LEDCHIP-LED0603")
      (footprint "eagle-import:CHIP-LED0603")
      (libsource (lib "eagle-import") (part "LEDCHIP-LED0603"))
    )
    (comp (ref "LED6")
      (value "LEDCHIP-LED0603")
      (footprint "eagle-import:CHIP-LED0603")
      (libsource (lib "eagle-import") (part "LEDCHIP-LED0603"))
    )
    (comp (ref "LED9")
      (value "LEDCHIP-LED0603")
      (footprint "eagle-import:CHIP-LED0603")
      (libsource (lib "eagle-import") (part "LEDCHIP-LED0603"))
    )
    (comp (ref "Q2")
      (value "BSS84")
      (footprint "eagle-import:SOT23")
      (libsource (lib "eagle-import") (part "BSS84"))
    )
    (comp (ref "Q4")
      (value "BSS123")
      (footprint "eagle-import:SOT23")
      (libsource (lib "eagle-import") (part "BSS123"))
    )
    (comp (ref "Q5")
      (value "BSS84")
      (footprint "eagle-import:SOT23")
      (libsource (lib "eagle-import") (part "BSS84"))
    )
    (comp (ref "R1")
      (value "0.2")
      (footprint "eagle-import:R0603-N")
      (libsource (lib "eagle-import") (part "RESISTOR0603-N"))
    )
    (comp (ref "R2")
      (value "10k")
      (footprint "eagle-import:R0603-N")
      (libsource (lib "eagle-import") (part "RESISTOR0603-N"))
    )
    (comp (ref "R3")
      (value "0.2")
      (footprint "eagle-import:R0603-N")
      (libsource (lib "eagle-import") (part "RESISTOR0603-N"))
    )
    (comp (ref "R4")
      (value "10k")
      (footprint "eagle-import:R0603-N")
      (libsource (lib "eagle-import") (part "RESISTOR0603-N"))
    )
    (comp (ref "R5")
      (value "RESISTOR0603-N")
      (footprint "eagle-import:R0603-N")
      (libsource (lib "eagle-import") (part "RESISTOR0603-N"))
    )
    (comp (ref "R6")
      (value "RESISTOR0603-N")
      (footprint "eagle-import:R0603-N")
      (libsource (lib "eagle-import") (part "RESISTOR0603-N"))
    )
    (comp (ref "R7")
      (value "100k")
      (footprint "eagle-import:R0603-N")
      (libsource (lib "eagle-import") (part "RESISTOR0603-N"))
    )
    (comp (ref "R8")
      (value "10k")
      (footprint "eagle-import:R0603-N")
      (libsource (lib "eagle-import") (part "RESISTOR0603-N"))
    )
    (comp (ref "R9")
      (value "10k")
      (footprint "eagle-import:R0603-N")
      (libsource (lib "eagle-import") (part "RESISTOR0603-N"))
    )
    (comp (ref "R10")
      (value "100k")
      (footprint "eagle-import:R0603-N")
      (libsource (lib "eagle-import") (part "RESISTOR0603-N"))
    )
    (comp (ref "R11")
      (value "56k 0.5%")
      (footprint "eagle-import:R0603-N")
      (libsource (lib "eagle-import") (part "RESISTOR0603-N"))
    )
    (comp (ref "R12")
      (value "56k 0.5%")
      (footprint "eagle-import:R0603-N")
      (libsource (lib "eagle-import") (part "RESISTOR0603-N"))
    )
    (comp (ref "R13")
      (value "22")
      (footprint "eagle-import:R0603-N")
      (libsource (lib "eagle-import") (part "RESISTOR0603-N"))
    )
    (comp (ref "R16")
      (value "10k")
      (footprint "eagle-import:R0603-N")
      (libsource (lib "eagle-import") (part "RESISTOR0603-N"))
    )
    (comp (ref "R17")
      (value "100k")
      (footprint "eagle-import:R0603-N")
      (libsource (lib "eagle-import") (part "RESISTOR0603-N"))
    )
    (comp (ref "R18")
      (value "RESISTOR0603-N")
      (footprint "eagle-import:R0603-N")
      (libsource (lib "eagle-import") (part "RESISTOR0603-N"))
    )
    (comp (ref "R19")
      (value "RESISTOR0603-N")
      (footprint "eagle-import:R0603-N")
      (libsource (lib "eagle-import") (part "RESISTOR0603-N"))
    )
    (comp (ref "R22")
      (value "100k")
      (footprint "eagle-import:R0603-N")
      (libsource (lib "eagle-import") (part "RESISTOR0603-N"))
    )
    (comp (ref "R23")
      (value "4k7")
      (footprint "eagle-import:R0603-N")
      (libsource (lib "eagle-import") (part "RESISTOR0603-N"))
    )
    (comp (ref "R24")
      (value "4k7")
      (footprint "eagle-import:R0603-N")
      (libsource (lib "eagle-import") (part "RESISTOR0603-N"))
    )
    (comp (ref "R25")
      (value "10k")
      (footprint "eagle-import:R0603-N")
      (libsource (lib "eagle-import") (part "RESISTOR0603-N"))
    )
    (comp (ref "R26")
      (value "1.8k")
      (footprint "eagle-import:R0603-N")
      (libsource (lib "eagle-import") (part "RESISTOR0603-N"))
    )
    (comp (ref "R27")
      (value "2.2k")
      (footprint "eagle-import:R0603-N")
      (libsource (lib "eagle-import") (part "RESISTOR0603-N"))
    )
    (comp (ref "R28")
      (value "RESISTOR0603-N")
      (footprint "eagle-import:R0603-N")
      (libsource (lib "eagle-import") (part "RESISTOR0603-N"))
    )
    (comp (ref "R29")
      (value "RESISTOR0603-N")
      (footprint "eagle-import:R0603-N")
      (libsource (lib "eagle-import") (part "RESISTOR0603-N"))
    )
    (comp (ref "R32")
      (value "RESISTOR0603-N")
      (footprint "eagle-import:R0603-N")
      (libsource (lib "eagle-import") (part "RESISTOR0603-N"))
    )
    (comp (ref "TP3")
      (value "PTR1B1,27")
      (footprint "eagle-import:B1,27")
      (libsource (lib "eagle-import") (part "PTR1B1,27"))
    )
    (comp (ref "TP5")
      (value "PTR1B1,27")
      (footprint "eagle-import:B1,27")
      (libsource (lib "eagle-import") (part "PTR1B1,27"))
    )
    (comp (ref "TP6")
      (value "PTR1B1,27")
      (footprint "eagle-import:B1,27")
      (libsource (lib "eagle-import") (part "PTR1B1,27"))
    )
    (comp (ref "TP7")
      (value "PTR1B1,27")
      (footprint "eagle-import:B1,27")
      (libsource (lib "eagle-import") (part "PTR1B1,27"))
    )
    (comp (ref "TP8")
      (value "PTR1B1,27")
      (footprint "eagle-import:B1,27")
      (libsource (lib "eagle-import") (part "PTR1B1,27"))
    )
    (comp (ref "TP9")
      (value "PTR1B1,27")
      (footprint "eagle-import:B1,27")
      (libsource (lib "eagle-import") (part "PTR1B1,27"))
    )
    (comp (ref "TP10")
      (value "PTR1B1,27")
      (footprint "eagle-import:B1,27")
      (libsource (lib "eagle-import") (part "PTR1B1,27"))
    )
    (comp (ref "TP11")
      (value "PTR1B1,27")
      (footprint "eagle-import:B1,27")
      (libsource (lib "eagle-import") (part "PTR1B1,27"))
    )
    (comp (ref "TP12")
      (value "PTR1B1,27")
      (footprint "eagle-import:B1,27")
      (libsource (lib "eagle-import") (part "PTR1B1,27"))
    )
    (comp (ref "TP13")
      (value "PTR1B1,27")
      (footprint "eagle-import:B1,27")
      (libsource (lib "eagle-import") (part "PTR1B1,27"))
    )
    (comp (ref "TP14")
      (value "PTR1B1,27")
      (footprint "eagle-import:B1,27")
      (libsource (lib "eagle-import") (part "PTR1B1,27"))
    )
    (comp (ref "TP15")
      (value "PTR1B1,27")
      (footprint "eagle-import:B1,27")
      (libsource (lib "eagle-import") (part "PTR1B1,27"))
    )
    (comp (ref "TP16")
      (value "PTR1B1,27")
      (footprint "eagle-import:B1,27")
      (libsource (lib "eagle-import") (part "PTR1B1,27"))
    )
    (comp (ref "TP17")
      (value "PTR1B1,27")
      (footprint "eagle-import:B1,27")
      (libsource (lib "eagle-import") (part "PTR1B1,27"))
    )
    (comp (ref "TP18")
      (value "PTR1B1,27")
      (footprint "eagle-import:B1,27")
      (libsource (lib "eagle-import") (part "PTR1B1,27"))
    )
    (comp (ref "TP19")
      (value "PTR1B1,27")
      (footprint "eagle-import:B1,27")
      (libsource (lib "eagle-import") (part "PTR1B1,27"))
    )
    (comp (ref "TP20")
      (value "PTR1B1,27")
      (footprint "eagle-import:B1,27")
      (libsource (lib "eagle-import") (part "PTR1B1,27"))
    )
    (comp (ref "TP21")
      (value "PTR1B1,27")
      (footprint "eagle-import:B1,27")
      (libsource (lib "eagle-import") (part "PTR1B1,27"))
    )
    (comp (ref "TP22")
      (value "PTR1B1,27")
      (footprint "eagle-import:B1,27")
      (libsource (lib "eagle-import") (part "PTR1B1,27"))
    )
    (comp (ref "TP23")
      (value "PTR1B1,27")
      (footprint "eagle-import:B1,27")
      (libsource (lib "eagle-import") (part "PTR1B1,27"))
    )
    (comp (ref "TP24")
      (value "PTR1B1,27")
      (footprint "eagle-import:B1,27")
      (libsource (lib "eagle-import") (part "PTR1B1,27"))
    )
    (comp (ref "TP25")
      (value "PTR1B1,27")
      (footprint "eagle-import:B1,27")
      (libsource (lib "eagle-import") (part "PTR1B1,27"))
    )
    (comp (ref "X1")
      (value "SHIELD-26X26")
      (footprint "eagle-import:SHIELD-26X26")
      (libsource (lib "eagle-import") (part "SHIELD-26X26"))
    )
    (comp (ref "X2")
      (value "SHIELD-26X26")
      (footprint "eagle-import:SHIELD-26X26")
      (libsource (lib "eagle-import") (part "SHIELD-26X26"))
    )
    (comp (ref "X3")
      (value "LFTCXO070")
      (footprint "eagle-import:260-SERIES")
      (libsource (lib "eagle-import") (part "LFTCXO070"))
    )
    (comp (ref "X4")
      (value "LFTCXO070")
      (footprint "eagle-import:260-SERIES")
      (libsource (lib "eagle-import") (part "LFTCXO070"))
    )
    (comp (ref "X5")
      (value "BU-SMA-V")
      (footprint "eagle-import:BU-SMA-V")
      (libsource (lib "eagle-import") (part "BU-SMA-V"))
    )
    (comp (ref "X6")
      (value "BU-SMA-V")
      (footprint "eagle-import:BU-SMA-V")
      (libsource (lib "eagle-import") (part "BU-SMA-V"))
    )
    (comp (ref "X7")
      (value "BU-SMA-V")
      (footprint "eagle-import:BU-SMA-V")
      (libsource (lib "eagle-import") (part "BU-SMA-V"))
    )
    (comp (ref "X8")
      (value "BU-SMA-V")
      (footprint "eagle-import:BU-SMA-V")
      (libsource (lib "eagle-import") (part "BU-SMA-V"))
    )
    (comp (ref "X9")
      (value "BU-SMA-V")
      (footprint "eagle-import:BU-SMA-V")
      (libsource (lib "eagle-import") (part "BU-SMA-V"))
    )
    (comp (ref "X10")
      (value "BU-SMA-V")
      (footprint "eagle-import:BU-SMA-V")
      (libsource (lib "eagle-import") (part "BU-SMA-V"))
    )
    (comp (ref "X11")
      (value "BU-SMA-V")
      (footprint "eagle-import:BU-SMA-V")
      (libsource (lib "eagle-import") (part "BU-SMA-V"))
    )
    (comp (ref "X12")
      (value "BU-SMA-V")
      (footprint "eagle-import:BU-SMA-V")
      (libsource (lib "eagle-import") (part "BU-SMA-V"))
    )
    (comp (ref "X13")
      (value "BU-SMA-V")
      (footprint "eagle-import:BU-SMA-V")
      (libsource (lib "eagle-import") (part "BU-SMA-V"))
    )
    (comp (ref "X14")
      (value "BU-SMA-V")
      (footprint "eagle-import:BU-SMA-V")
      (libsource (lib "eagle-import") (part "BU-SMA-V"))
    )
    (comp (ref "X15")
      (value "BU-SMA-V")
      (footprint "eagle-import:BU-SMA-V")
      (libsource (lib "eagle-import") (part "BU-SMA-V"))
    )
    (comp (ref "X16")
      (value "BU-SMA-V")
      (footprint "eagle-import:BU-SMA-V")
      (libsource (lib "eagle-import") (part "BU-SMA-V"))
    )
    (comp (ref "X17")
      (value "BU-SMA-V")
      (footprint "eagle-import:BU-SMA-V")
      (libsource (lib "eagle-import") (part "BU-SMA-V"))
    )
    (comp (ref "X18")
      (value "BU-SMA-V")
      (footprint "eagle-import:BU-SMA-V")
      (libsource (lib "eagle-import") (part "BU-SMA-V"))
    )
  )
  (nets
    (net (code "1") (name "3V3{slash}FMCU") (class "Default")
      (node (ref "C105") (pin "1") (pinfunction "1_1") (pintype "passive"))
      (node (ref "C38") (pin "1") (pinfunction "1_1") (pintype "passive"))
      (node (ref "C39") (pin "1") (pinfunction "1_1") (pintype "passive"))
      (node (ref "C51") (pin "1") (pinfunction "1_1") (pintype "passive"))
      (node (ref "C54") (pin "1") (pinfunction "1_1") (pintype "passive"))
      (node (ref "C67") (pin "1") (pinfunction "1_1") (pintype "passive"))
      (node (ref "C68") (pin "1") (pinfunction "1_1") (pintype "passive"))
      (node (ref "C72") (pin "1") (pinfunction "1_1") (pintype "passive"))
      (node (ref "C73") (pin "1") (pinfunction "1_1") (pintype "passive"))
      (node (ref "C78") (pin "1") (pinfunction "1_1") (pintype "passive"))
      (node (ref "C79") (pin "1") (pinfunction "1_1") (pintype "passive"))
      (node (ref "C81") (pin "1") (pinfunction "1_1") (pintype "passive"))
      (node (ref "C82") (pin "1") (pinfunction "1_1") (pintype "passive"))
      (node (ref "C83") (pin "1") (pinfunction "1_1") (pintype "passive"))
      (node (ref "C92") (pin "1") (pinfunction "1_1") (pintype "passive"))
      (node (ref "IC11") (pin "1") (pinfunction "VDDIO_1") (pintype "bidirectional"))
      (node (ref "IC11") (pin "13") (pinfunction "VDD_13") (pintype "bidirectional"))
      (node (ref "IC11") (pin "22") (pinfunction "~{CS}_22") (pintype "bidirectional"))
      (node (ref "IC11") (pin "8") (pinfunction "VDDIO_8") (pintype "bidirectional"))
      (node (ref "IC12") (pin "10") (pinfunction "OE_10") (pintype "bidirectional"))
      (node (ref "IC12") (pin "2") (pinfunction "VCCA_2") (pintype "bidirectional"))
      (node (ref "IC13") (pin "3") (pinfunction "WDT_3") (pintype "input"))
      (node (ref "IC13") (pin "4") (pinfunction "VDD_4") (pintype "input"))
      (node (ref "IC14") (pin "4") (pinfunction "V+_4") (pintype "power_in"))
      (node (ref "IC16") (pin "7") (pinfunction "A0_7") (pintype "input"))
      (node (ref "IC16") (pin "8") (pinfunction "VCC_8") (pintype "power_in"))
      (node (ref "IC18") (pin "8") (pinfunction "VCC_8") (pintype "power_in"))
      (node (ref "IC5") (pin "19") (pinfunction "VCCB_19") (pintype "bidirectional"))
      (node (ref "IC6") (pin "19") (pinfunction "VCCB_19") (pintype "bidirectional"))
      (node (ref "IC9") (pin "11") (pinfunction "VDD_11") (pintype "bidirectional"))
      (node (ref "IC9") (pin "2") (pinfunction "VDDA_2") (pintype "bidirectional"))
      (node (ref "IC9") (pin "26") (pinfunction "VDD_26") (pintype "bidirectional"))
      (node (ref "IC9") (pin "37") (pinfunction "VBAT_37") (pintype "bidirectional"))
      (node (ref "IC9") (pin "42") (pinfunction "VDD_42") (pintype "bidirectional"))
      (node (ref "IC9") (pin "54") (pinfunction "VDD_54") (pintype "bidirectional"))
      (node (ref "J3") (pin "1") (pinfunction "VCC_1") (pintype "power_in"))
      (node (ref "JP4") (pin "2") (pinfunction "2_2") (pintype "passive"))
      (node (ref "R14") (pin "2") (pinfunction "P$2_2") (pintype "passive"))
      (node (ref "R15") (pin "2") (pinfunction "P$2_2") (pintype "passive"))
      (node (ref "R20") (pin "2") (pinfunction "P$2_2") (pintype "passive"))
      (node (ref "R21") (pin "2") (pinfunction "P$2_2") (pintype "passive"))
      (node (ref "R23") (pin "2") (pinfunction "P$2_2") (pintype "passive"))
      (node (ref "R24") (pin "2") (pinfunction "P$2_2") (pintype "passive"))
      (node (ref "SV2") (pin "49") (pinfunction "49_49") (pintype "passive"))
      (node (ref "TP2") (pin "TP") (pinfunction "TP_TP") (pintype "input"))
    )
    (net (code "2") (name "3V3{slash}SYS") (class "Default")
      (node (ref "SV3") (pin "27") (pinfunction "27_27") (pintype "passive"))
      (node (ref "SV3") (pin "28") (pinfunction "28_28") (pintype "passive"))
    )
    (net (code "3") (name "5V{slash}CAM") (class "Default")
      (node (ref "C87") (pin "1") (pinfunction "1_1") (pintype "passive"))
      (node (ref "IC12") (pin "19") (pinfunction "VCCB_19") (pintype "bidirectional"))
      (node (ref "J2") (pin "1") (pinfunction "+_1") (pintype "bidirectional"))
      (node (ref "JP12") (pin "4") (pinfunction "4_4") (pintype "passive"))
      (node (ref "SV2") (pin "50") (pinfunction "50_50") (pintype "passive"))
      (node (ref "TP4") (pin "TP") (pinfunction "TP_TP") (pintype "input"))
    )
    (net (code "4") (name "5V{slash}RX") (class "Default")
      (node (ref "JP14") (pin "2") (pinfunction "2_2") (pintype "passive"))
      (node (ref "JP3") (pin "2") (pinfunction "2_2") (pintype "passive"))
      (node (ref "R1") (pin "1") (pinfunction "P$1_1") (pintype "passive"))
      (node (ref "SV2") (pin "51") (pinfunction "51_51") (pintype "passive"))
    )
    (net (code "5") (name "5V{slash}SYS") (class "Default")
      (node (ref "C10") (pin "1") (pinfunction "1_1") (pintype "passive"))
      (node (ref "IC4") (pin "3") (pinfunction "IN_3") (pintype "input"))
      (node (ref "J1") (pin "1") (pinfunction "+_1") (pintype "bidirectional"))
      (node (ref "JP13") (pin "1") (pinfunction "1_1") (pintype "passive"))
      (node (ref "JP14") (pin "1") (pinfunction "1_1") (pintype "passive"))
      (node (ref "SV3") (pin "25") (pinfunction "25_25") (pintype "passive"))
      (node (ref "SV3") (pin "26") (pinfunction "26_26") (pintype "passive"))
      (node (ref "TP1") (pin "TP") (pinfunction "TP_TP") (pintype "input"))
    )
    (net (code "6") (name "5V{slash}TX") (class "Default")
      (node (ref "JP10") (pin "1") (pinfunction "1_1") (pintype "passive"))
      (node (ref "JP13") (pin "2") (pinfunction "2_2") (pintype "passive"))
      (node (ref "JP2") (pin "1") (pinfunction "1_1") (pintype "passive"))
      (node (ref "Q5") (pin "2") (pinfunction "S_2") (pintype "passive"))
      (node (ref "R22") (pin "2") (pinfunction "P$2_2") (pintype "passive"))
      (node (ref "R3") (pin "1") (pinfunction "P$1_1") (pintype "passive"))
      (node (ref "SV2") (pin "52") (pinfunction "52_52") (pintype "passive"))
    )
    (net (code "7") (name "9AXIS{slash}SCL") (class "Default")
      (node (ref "IC11") (pin "23") (pinfunction "SCLK_23") (pintype "bidirectional"))
      (node (ref "IC9") (pin "59") (pinfunction "PE4_59") (pintype "bidirectional"))
      (node (ref "R21") (pin "1") (pinfunction "P$1_1") (pintype "passive"))
    )
    (net (code "8") (name "9AXIS{slash}SDA") (class "Default")
      (node (ref "IC11") (pin "24") (pinfunction "SDA/MOSI_24") (pintype "bidirectional"))
      (node (ref "IC9") (pin "60") (pinfunction "PE5_60") (pintype "bidirectional"))
      (node (ref "R20") (pin "1") (pinfunction "P$1_1") (pintype "passive"))
    )
    (net (code "9") (name "ANT{slash}GATE") (class "Default")
      (node (ref "IC9") (pin "57") (pinfunction "PB5_57") (pintype "bidirectional"))
      (node (ref "SV3") (pin "19") (pinfunction "19_19") (pintype "passive"))
    )
    (net (code "10") (name "ANT{slash}SW") (class "Default")
      (node (ref "IC9") (pin "58") (pinfunction "PB4_58") (pintype "bidirectional"))
      (node (ref "SV3") (pin "21") (pinfunction "21_21") (pintype "passive"))
    )
    (net (code "11") (name "CAM{slash}RXD") (class "Default")
      (node (ref "IC12") (pin "4") (pinfunction "A3_4") (pintype "bidirectional"))
      (node (ref "IC9") (pin "13") (pinfunction "PC7_13") (pintype "bidirectional"))
    )
    (net (code "12") (name "CAM{slash}TXD") (class "Default")
      (node (ref "IC12") (pin "5") (pinfunction "A4_5") (pintype "bidirectional"))
      (node (ref "IC9") (pin "14") (pinfunction "PC6_14") (pintype "bidirectional"))
    )
    (net (code "13") (name "GND") (class "Default")
      (node (ref "C1") (pin "2") (pinfunction "2_2") (pintype "passive"))
      (node (ref "C10") (pin "2") (pinfunction "2_2") (pintype "passive"))
      (node (ref "C100") (pin "2") (pinfunction "2_2") (pintype "passive"))
      (node (ref "C101") (pin "2") (pinfunction "2_2") (pintype "passive"))
      (node (ref "C103") (pin "2") (pinfunction "2_2") (pintype "passive"))
      (node (ref "C104") (pin "2") (pinfunction "2_2") (pintype "passive"))
      (node (ref "C105") (pin "2") (pinfunction "2_2") (pintype "passive"))
      (node (ref "C106") (pin "2") (pinfunction "2_2") (pintype "passive"))
      (node (ref "C11") (pin "2") (pinfunction "2_2") (pintype "passive"))
      (node (ref "C12") (pin "2") (pinfunction "2_2") (pintype "passive"))
      (node (ref "C13") (pin "2") (pinfunction "2_2") (pintype "passive"))
      (node (ref "C14") (pin "2") (pinfunction "2_2") (pintype "passive"))
      (node (ref "C15") (pin "1") (pinfunction "1_1") (pintype "passive"))
      (node (ref "C16") (pin "1") (pinfunction "1_1") (pintype "passive"))
      (node (ref "C17") (pin "2") (pinfunction "2_2") (pintype "passive"))
      (node (ref "C18") (pin "2") (pinfunction "2_2") (pintype "passive"))
      (node (ref "C19") (pin "1") (pinfunction "1_1") (pintype "passive"))
      (node (ref "C2") (pin "2") (pinfunction "2_2") (pintype "passive"))
      (node (ref "C20") (pin "1") (pinfunction "1_1") (pintype "passive"))
      (node (ref "C21") (pin "2") (pinfunction "2_2") (pintype "passive"))
      (node (ref "C23") (pin "1") (pinfunction "1_1") (pintype "passive"))
      (node (ref "C25") (pin "1") (pinfunction "1_1") (pintype "passive"))
      (node (ref "C26") (pin "1") (pinfunction "1_1") (pintype "passive"))
      (node (ref "C27") (pin "1") (pinfunction "1_1") (pintype "passive"))
      (node (ref "C28") (pin "1") (pinfunction "1_1") (pintype "passive"))
      (node (ref "C29") (pin "1") (pinfunction "1_1") (pintype "passive"))
      (node (ref "C3") (pin "2") (pinfunction "2_2") (pintype "passive"))
      (node (ref "C30") (pin "1") (pinfunction "1_1") (pintype "passive"))
      (node (ref "C31") (pin "1") (pinfunction "1_1") (pintype "passive"))
      (node (ref "C32") (pin "1") (pinfunction "1_1") (pintype "passive"))
      (node (ref "C33") (pin "1") (pinfunction "1_1") (pintype "passive"))
      (node (ref "C34") (pin "1") (pinfunction "1_1") (pintype "passive"))
      (node (ref "C35") (pin "1") (pinfunction "1_1") (pintype "passive"))
      (node (ref "C36") (pin "1") (pinfunction "1_1") (pintype "passive"))
      (node (ref "C38") (pin "2") (pinfunction "2_2") (pintype "passive"))
      (node (ref "C39") (pin "2") (pinfunction "2_2") (pintype "passive"))
      (node (ref "C4") (pin "2") (pinfunction "2_2") (pintype "passive"))
      (node (ref "C40") (pin "1") (pinfunction "1_1") (pintype "passive"))
      (node (ref "C43") (pin "1") (pinfunction "1_1") (pintype "passive"))
      (node (ref "C44") (pin "1") (pinfunction "1_1") (pintype "passive"))
      (node (ref "C46") (pin "1") (pinfunction "1_1") (pintype "passive"))
      (node (ref "C48") (pin "2") (pinfunction "2_2") (pintype "passive"))
      (node (ref "C49") (pin "2") (pinfunction "2_2") (pintype "passive"))
      (node (ref "C5") (pin "2") (pinfunction "2_2") (pintype "passive"))
      (node (ref "C50") (pin "1") (pinfunction "1_1") (pintype "passive"))
      (node (ref "C51") (pin "2") (pinfunction "2_2") (pintype "passive"))
      (node (ref "C52") (pin "1") (pinfunction "1_1") (pintype "passive"))
      (node (ref "C53") (pin "2") (pinfunction "2_2") (pintype "passive"))
      (node (ref "C54") (pin "2") (pinfunction "2_2") (pintype "passive"))
      (node (ref "C55") (pin "2") (pinfunction "2_2") (pintype "passive"))
      (node (ref "C56") (pin "1") (pinfunction "1_1") (pintype "passive"))
      (node (ref "C58") (pin "2") (pinfunction "2_2") (pintype "passive"))
      (node (ref "C6") (pin "2") (pinfunction "2_2") (pintype "passive"))
      (node (ref "C61") (pin "2") (pinfunction "2_2") (pintype "passive"))
      (node (ref "C62") (pin "2") (pinfunction "2_2") (pintype "passive"))
      (node (ref "C63") (pin "2") (pinfunction "2_2") (pintype "passive"))
      (node (ref "C64") (pin "2") (pinfunction "2_2") (pintype "passive"))
      (node (ref "C65") (pin "2") (pinfunction "2_2") (pintype "passive"))
      (node (ref "C66") (pin "1") (pinfunction "1_1") (pintype "passive"))
      (node (ref "C67") (pin "2") (pinfunction "2_2") (pintype "passive"))
      (node (ref "C68") (pin "2") (pinfunction "2_2") (pintype "passive"))
      (node (ref "C7") (pin "2") (pinfunction "2_2") (pintype "passive"))
      (node (ref "C72") (pin "2") (pinfunction "2_2") (pintype "passive"))
      (node (ref "C73") (pin "2") (pinfunction "2_2") (pintype "passive"))
      (node (ref "C74") (pin "2") (pinfunction "2_2") (pintype "passive"))
      (node (ref "C75") (pin "2") (pinfunction "2_2") (pintype "passive"))
      (node (ref "C76") (pin "2") (pinfunction "2_2") (pintype "passive"))
      (node (ref "C77") (pin "2") (pinfunction "2_2") (pintype "passive"))
      (node (ref "C78") (pin "2") (pinfunction "2_2") (pintype "passive"))
      (node (ref "C79") (pin "2") (pinfunction "2_2") (pintype "passive"))
      (node (ref "C80") (pin "2") (pinfunction "2_2") (pintype "passive"))
      (node (ref "C81") (pin "2") (pinfunction "2_2") (pintype "passive"))
      (node (ref "C82") (pin "2") (pinfunction "2_2") (pintype "passive"))
      (node (ref "C83") (pin "2") (pinfunction "2_2") (pintype "passive"))
      (node (ref "C84") (pin "2") (pinfunction "2_2") (pintype "passive"))
      (node (ref "C85") (pin "2") (pinfunction "2_2") (pintype "passive"))
      (node (ref "C86") (pin "1") (pinfunction "1_1") (pintype "passive"))
      (node (ref "C87") (pin "2") (pinfunction "2_2") (pintype "passive"))
      (node (ref "C88") (pin "1") (pinfunction "1_1") (pintype "passive"))
      (node (ref "C89") (pin "1") (pinfunction "1_1") (pintype "passive"))
      (node (ref "C9") (pin "2") (pinfunction "2_2") (pintype "passive"))
      (node (ref "C92") (pin "2") (pinfunction "2_2") (pintype "passive"))
      (node (ref "C93") (pin "2") (pinfunction "2_2") (pintype "passive"))
      (node (ref "C94") (pin "2") (pinfunction "2_2") (pintype "passive"))
      (node (ref "C95") (pin "2") (pinfunction "2_2") (pintype "passive"))
      (node (ref "C96") (pin "2") (pinfunction "2_2") (pintype "passive"))
      (node (ref "C97") (pin "2") (pinfunction "2_2") (pintype "passive"))
      (node (ref "C98") (pin "2") (pinfunction "2_2") (pintype "passive"))
      (node (ref "C99") (pin "2") (pinfunction "2_2") (pintype "passive"))
      (node (ref "FL1") (pin "A") (pinfunction "GND_A") (pintype "bidirectional"))
      (node (ref "FL1") (pin "C") (pinfunction "GND_C") (pintype "bidirectional"))
      (node (ref "FL1") (pin "D") (pinfunction "GND_D") (pintype "bidirectional"))
      (node (ref "FL1") (pin "F") (pinfunction "GND_F") (pintype "bidirectional"))
      (node (ref "FL2") (pin "1") (pinfunction "G1_1") (pintype "bidirectional"))
      (node (ref "FL2") (pin "3") (pinfunction "G2_3") (pintype "bidirectional"))
      (node (ref "FL2") (pin "4") (pinfunction "G3_4") (pintype "bidirectional"))
      (node (ref "FL2") (pin "5") (pinfunction "G4_5") (pintype "bidirectional"))
      (node (ref "FL2") (pin "7") (pinfunction "G6_7") (pintype "bidirectional"))
      (node (ref "FL2") (pin "8") (pinfunction "G5_8") (pintype "bidirectional"))
      (node (ref "FL3") (pin "1") (pinfunction "G6_1") (pintype "bidirectional"))
      (node (ref "FL3") (pin "3") (pinfunction "G5_3") (pintype "bidirectional"))
      (node (ref "FL3") (pin "4") (pinfunction "G4_4") (pintype "bidirectional"))
      (node (ref "FL3") (pin "5") (pinfunction "G3_5") (pintype "bidirectional"))
      (node (ref "FL3") (pin "7") (pinfunction "G2_7") (pintype "bidirectional"))
      (node (ref "FL3") (pin "8") (pinfunction "G1_8") (pintype "bidirectional"))
      (node (ref "G1") (pin "P$3") (pinfunction "1_P$3") (pintype "passive"))
      (node (ref "G1") (pin "P$4") (pinfunction "2_P$4") (pintype "passive"))
      (node (ref "IC1") (pin "2") (pinfunction "GND_2") (pintype "passive"))
      (node (ref "IC10") (pin "2") (pinfunction "2_2") (pintype "bidirectional"))
      (node (ref "IC10") (pin "4") (pinfunction "4_4") (pintype "bidirectional"))
      (node (ref "IC11") (pin "11") (pinfunction "FSYNC_11") (pintype "bidirectional"))
      (node (ref "IC11") (pin "18") (pinfunction "GND_18") (pintype "bidirectional"))
      (node (ref "IC11") (pin "20") (pinfunction "GND_20") (pintype "bidirectional"))
      (node (ref "IC11") (pin "9") (pinfunction "AD0/MISO_9") (pintype "bidirectional"))
      (node (ref "IC12") (pin "1") (pinfunction "A1_1") (pintype "bidirectional"))
      (node (ref "IC12") (pin "11") (pinfunction "GND_11") (pintype "bidirectional"))
      (node (ref "IC12") (pin "3") (pinfunction "A2_3") (pintype "bidirectional"))
      (node (ref "IC12") (pin "6") (pinfunction "A5_6") (pintype "bidirectional"))
      (node (ref "IC12") (pin "7") (pinfunction "A6_7") (pintype "bidirectional"))
      (node (ref "IC12") (pin "8") (pinfunction "A7_8") (pintype "bidirectional"))
      (node (ref "IC12") (pin "9") (pinfunction "A8_9") (pintype "bidirectional"))
      (node (ref "IC13") (pin "2") (pinfunction "GND_2") (pintype "input"))
      (node (ref "IC13") (pin "5") (pinfunction "WDR_5") (pintype "input"))
      (node (ref "IC14") (pin "2") (pinfunction "GND_2") (pintype "power_in"))
      (node (ref "IC14") (pin "3") (pinfunction "ADD1_3") (pintype "passive"))
      (node (ref "IC14") (pin "5") (pinfunction "ADD0_5") (pintype "passive"))
      (node (ref "IC15") (pin "GND1") (pinfunction "GND1_GND1") (pintype "bidirectional"))
      (node (ref "IC15") (pin "GND2") (pinfunction "GND2_GND2") (pintype "bidirectional"))
      (node (ref "IC16") (pin "4") (pinfunction "GND_4") (pintype "power_in"))
      (node (ref "IC16") (pin "5") (pinfunction "A2_5") (pintype "input"))
      (node (ref "IC16") (pin "6") (pinfunction "A1_6") (pintype "input"))
      (node (ref "IC16") (pin "EP") (pinfunction "GND_EP") (pintype "power_in"))
      (node (ref "IC17") (pin "10") (pinfunction "PDOWN_10") (pintype "input"))
      (node (ref "IC17") (pin "EXP") (pinfunction "GND_EXP") (pintype "power_in"))
      (node (ref "IC18") (pin "4") (pinfunction "GND_4") (pintype "power_in"))
      (node (ref "IC18") (pin "5") (pinfunction "A2_5") (pintype "input"))
      (node (ref "IC18") (pin "6") (pinfunction "A1_6") (pintype "input"))
      (node (ref "IC18") (pin "7") (pinfunction "A0_7") (pintype "input"))
      (node (ref "IC18") (pin "EP") (pinfunction "GND_EP") (pintype "power_in"))
      (node (ref "IC2") (pin "2") (pinfunction "GND_2") (pintype "passive"))
      (node (ref "IC3") (pin "6") (pinfunction "VSS_6") (pintype "bidirectional"))
      (node (ref "IC4") (pin "1") (pinfunction "GND_1") (pintype "input"))
      (node (ref "IC5") (pin "11") (pinfunction "GND_11") (pintype "bidirectional"))
      (node (ref "IC6") (pin "11") (pinfunction "GND_11") (pintype "bidirectional"))
      (node (ref "IC7") (pin "19") (pinfunction "LNA_P_19") (pintype "bidirectional"))
      (node (ref "IC7") (pin "20") (pinfunction "LNA_N_20") (pintype "bidirectional"))
      (node (ref "IC7") (pin "30") (pinfunction "XOSC_Q1_30") (pintype "bidirectional"))
      (node (ref "IC7") (pin "33") (pinfunction "GND_PAD_33") (pintype "bidirectional"))
      (node (ref "IC77") (pin "3") (pinfunction "GND_3") (pintype "power_in"))
      (node (ref "IC8") (pin "30") (pinfunction "XOSC_Q1_30") (pintype "bidirectional"))
      (node (ref "IC8") (pin "33") (pinfunction "GND_PAD_33") (pintype "bidirectional"))
      (node (ref "IC9") (pin "12") (pinfunction "GND_12") (pintype "bidirectional"))
      (node (ref "IC9") (pin "27") (pinfunction "GND_27") (pintype "bidirectional"))
      (node (ref "IC9") (pin "3") (pinfunction "GNDA_3") (pintype "bidirectional"))
      (node (ref "IC9") (pin "35") (pinfunction "GNDX_35") (pintype "bidirectional"))
      (node (ref "IC9") (pin "39") (pinfunction "GND_39") (pintype "bidirectional"))
      (node (ref "IC9") (pin "55") (pinfunction "GND_55") (pintype "bidirectional"))
      (node (ref "J1") (pin "2") (pinfunction "-_2") (pintype "bidirectional"))
      (node (ref "J2") (pin "2") (pinfunction "-_2") (pintype "bidirectional"))
      (node (ref "J3") (pin "3") (pinfunction "GND1_3") (pintype "power_in"))
      (node (ref "J3") (pin "5") (pinfunction "GND2_5") (pintype "power_in"))
      (node (ref "J3") (pin "9") (pinfunction "GNDD_9") (pintype "power_in"))
      (node (ref "JP1") (pin "2") (pinfunction "2_2") (pintype "passive"))
      (node (ref "JP12") (pin "1") (pinfunction "1_1") (pintype "passive"))
      (node (ref "JP5") (pin "2") (pinfunction "2_2") (pintype "passive"))
      (node (ref "JP6") (pin "2") (pinfunction "2_2") (pintype "passive"))
      (node (ref "L10") (pin "1") (pinfunction "P$1_1") (pintype "passive"))
      (node (ref "L11") (pin "1") (pinfunction "P$1_1") (pintype "passive"))
      (node (ref "L15") (pin "1") (pinfunction "P$1_1") (pintype "passive"))
      (node (ref "L6") (pin "1") (pinfunction "P$1_1") (pintype "passive"))
      (node (ref "LED7") (pin "C") (pinfunction "C_C") (pintype "passive"))
      (node (ref "LED8") (pin "C") (pinfunction "C_C") (pintype "passive"))
      (node (ref "Q4") (pin "2") (pinfunction "S_2") (pintype "passive"))
      (node (ref "R11") (pin "2") (pinfunction "P$2_2") (pintype "passive"))
      (node (ref "R12") (pin "2") (pinfunction "P$2_2") (pintype "passive"))
      (node (ref "R18") (pin "2") (pinfunction "P$2_2") (pintype "passive"))
      (node (ref "R19") (pin "2") (pinfunction "P$2_2") (pintype "passive"))
      (node (ref "R25") (pin "1") (pinfunction "P$1_1") (pintype "passive"))
      (node (ref "R28") (pin "1") (pinfunction "P$1_1") (pintype "passive"))
      (node (ref "R29") (pin "1") (pinfunction "P$1_1") (pintype "passive"))
      (node (ref "R32") (pin "2") (pinfunction "P$2_2") (pintype "passive"))
      (node (ref "R5") (pin "2") (pinfunction "P$2_2") (pintype "passive"))
      (node (ref "R6") (pin "2") (pinfunction "P$2_2") (pintype "passive"))
      (node (ref "SV3") (pin "29") (pinfunction "29_29") (pintype "passive"))
      (node (ref "SV3") (pin "30") (pinfunction "30_30") (pintype "passive"))
      (node (ref "SV3") (pin "31") (pinfunction "31_31") (pintype "passive"))
      (node (ref "SV3") (pin "32") (pinfunction "32_32") (pintype "passive"))
      (node (ref "TP25") (pin "TP") (pinfunction "TP_TP") (pintype "input"))
      (node (ref "X1") (pin "G1") (pinfunction "G_G1") (pintype "passive"))
      (node (ref "X1") (pin "G10") (pinfunction "G_G10") (pintype "passive"))
      (node (ref "X1") (pin "G11") (pinfunction "G_G11") (pintype "passive"))
      (node (ref "X1") (pin "G12") (pinfunction "G_G12") (pintype "passive"))
      (node (ref "X1") (pin "G13") (pinfunction "G_G13") (pintype "passive"))
      (node (ref "X1") (pin "G14") (pinfunction "G_G14") (pintype "passive"))
      (node (ref "X1") (pin "G15") (pinfunction "G_G15") (pintype "passive"))
      (node (ref "X1") (pin "G16") (pinfunction "G_G16") (pintype "passive"))
      (node (ref "X1") (pin "G17") (pinfunction "G_G17") (pintype "passive"))
      (node (ref "X1") (pin "G19") (pinfunction "G_G19") (pintype "passive"))
      (node (ref "X1") (pin "G2") (pinfunction "G_G2") (pintype "passive"))
      (node (ref "X1") (pin "G20") (pinfunction "G_G20") (pintype "passive"))
      (node (ref "X1") (pin "G21") (pinfunction "G_G21") (pintype "passive"))
      (node (ref "X1") (pin "G3") (pinfunction "G_G3") (pintype "passive"))
      (node (ref "X1") (pin "G4") (pinfunction "G_G4") (pintype "passive"))
      (node (ref "X1") (pin "G5") (pinfunction "G_G5") (pintype "passive"))
      (node (ref "X1") (pin "G6") (pinfunction "G_G6") (pintype "passive"))
      (node (ref "X1") (pin "G7") (pinfunction "G_G7") (pintype "passive"))
      (node (ref "X1") (pin "G8") (pinfunction "G_G8") (pintype "passive"))
      (node (ref "X1") (pin "G9") (pinfunction "G_G9") (pintype "passive"))
      (node (ref "X10") (pin "2") (pinfunction "2_2") (pintype "passive"))
      (node (ref "X10") (pin "3") (pinfunction "2_3") (pintype "passive"))
      (node (ref "X10") (pin "4") (pinfunction "2_4") (pintype "passive"))
      (node (ref "X10") (pin "5") (pinfunction "2_5") (pintype "passive"))
      (node (ref "X11") (pin "2") (pinfunction "2_2") (pintype "passive"))
      (node (ref "X11") (pin "3") (pinfunction "2_3") (pintype "passive"))
      (node (ref "X11") (pin "4") (pinfunction "2_4") (pintype "passive"))
      (node (ref "X11") (pin "5") (pinfunction "2_5") (pintype "passive"))
      (node (ref "X12") (pin "2") (pinfunction "2_2") (pintype "passive"))
      (node (ref "X12") (pin "3") (pinfunction "2_3") (pintype "passive"))
      (node (ref "X12") (pin "4") (pinfunction "2_4") (pintype "passive"))
      (node (ref "X12") (pin "5") (pinfunction "2_5") (pintype "passive"))
      (node (ref "X13") (pin "2") (pinfunction "2_2") (pintype "passive"))
      (node (ref "X13") (pin "3") (pinfunction "2_3") (pintype "passive"))
      (node (ref "X13") (pin "4") (pinfunction "2_4") (pintype "passive"))
      (node (ref "X13") (pin "5") (pinfunction "2_5") (pintype "passive"))
      (node (ref "X14") (pin "2") (pinfunction "2_2") (pintype "passive"))
      (node (ref "X14") (pin "3") (pinfunction "2_3") (pintype "passive"))
      (node (ref "X14") (pin "4") (pinfunction "2_4") (pintype "passive"))
      (node (ref "X14") (pin "5") (pinfunction "2_5") (pintype "passive"))
      (node (ref "X15") (pin "2") (pinfunction "2_2") (pintype "passive"))
      (node (ref "X15") (pin "3") (pinfunction "2_3") (pintype "passive"))
      (node (ref "X15") (pin "4") (pinfunction "2_4") (pintype "passive"))
      (node (ref "X15") (pin "5") (pinfunction "2_5") (pintype "passive"))
      (node (ref "X16") (pin "2") (pinfunction "2_2") (pintype "passive"))
      (node (ref "X16") (pin "3") (pinfunction "2_3") (pintype "passive"))
      (node (ref "X16") (pin "4") (pinfunction "2_4") (pintype "passive"))
      (node (ref "X16") (pin "5") (pinfunction "2_5") (pintype "passive"))
      (node (ref "X17") (pin "2") (pinfunction "2_2") (pintype "passive"))
      (node (ref "X17") (pin "3") (pinfunction "2_3") (pintype "passive"))
      (node (ref "X17") (pin "4") (pinfunction "2_4") (pintype "passive"))
      (node (ref "X17") (pin "5") (pinfunction "2_5") (pintype "passive"))
      (node (ref "X18") (pin "2") (pinfunction "2_2") (pintype "passive"))
      (node (ref "X18") (pin "3") (pinfunction "2_3") (pintype "passive"))
      (node (ref "X18") (pin "4") (pinfunction "2_4") (pintype "passive"))
      (node (ref "X18") (pin "5") (pinfunction "2_5") (pintype "passive"))
      (node (ref "X2") (pin "G1") (pinfunction "G_G1") (pintype "passive"))
      (node (ref "X2") (pin "G10") (pinfunction "G_G10") (pintype "passive"))
      (node (ref "X2") (pin "G11") (pinfunction "G_G11") (pintype "passive"))
      (node (ref "X2") (pin "G12") (pinfunction "G_G12") (pintype "passive"))
      (node (ref "X2") (pin "G13") (pinfunction "G_G13") (pintype "passive"))
      (node (ref "X2") (pin "G14") (pinfunction "G_G14") (pintype "passive"))
      (node (ref "X2") (pin "G15") (pinfunction "G_G15") (pintype "passive"))
      (node (ref "X2") (pin "G16") (pinfunction "G_G16") (pintype "passive"))
      (node (ref "X2") (pin "G17") (pinfunction "G_G17") (pintype "passive"))
      (node (ref "X2") (pin "G19") (pinfunction "G_G19") (pintype "passive"))
      (node (ref "X2") (pin "G2") (pinfunction "G_G2") (pintype "passive"))
      (node (ref "X2") (pin "G20") (pinfunction "G_G20") (pintype "passive"))
      (node (ref "X2") (pin "G21") (pinfunction "G_G21") (pintype "passive"))
      (node (ref "X2") (pin "G3") (pinfunction "G_G3") (pintype "passive"))
      (node (ref "X2") (pin "G4") (pinfunction "G_G4") (pintype "passive"))
      (node (ref "X2") (pin "G5") (pinfunction "G_G5") (pintype "passive"))
      (node (ref "X2") (pin "G6") (pinfunction "G_G6") (pintype "passive"))
      (node (ref "X2") (pin "G7") (pinfunction "G_G7") (pintype "passive"))
      (node (ref "X2") (pin "G8") (pinfunction "G_G8") (pintype "passive"))
      (node (ref "X2") (pin "G9") (pinfunction "G_G9") (pintype "passive"))
      (node (ref "X3") (pin "1") (pinfunction "GND_1") (pintype "power_in"))
      (node (ref "X3") (pin "3") (pinfunction "GND_3") (pintype "power_in"))
      (node (ref "X4") (pin "1") (pinfunction "GND_1") (pintype "power_in"))
      (node (ref "X4") (pin "3") (pinfunction "GND_3") (pintype "power_in"))
      (node (ref "X5") (pin "2") (pinfunction "2_2") (pintype "passive"))
      (node (ref "X5") (pin "3") (pinfunction "2_3") (pintype "passive"))
      (node (ref "X5") (pin "4") (pinfunction "2_4") (pintype "passive"))
      (node (ref "X5") (pin "5") (pinfunction "2_5") (pintype "passive"))
      (node (ref "X6") (pin "2") (pinfunction "2_2") (pintype "passive"))
      (node (ref "X6") (pin "3") (pinfunction "2_3") (pintype "passive"))
      (node (ref "X6") (pin "4") (pinfunction "2_4") (pintype "passive"))
      (node (ref "X6") (pin "5") (pinfunction "2_5") (pintype "passive"))
      (node (ref "X7") (pin "2") (pinfunction "2_2") (pintype "passive"))
      (node (ref "X7") (pin "3") (pinfunction "2_3") (pintype "passive"))
      (node (ref "X7") (pin "4") (pinfunction "2_4") (pintype "passive"))
      (node (ref "X7") (pin "5") (pinfunction "2_5") (pintype "passive"))
      (node (ref "X8") (pin "2") (pinfunction "2_2") (pintype "passive"))
      (node (ref "X8") (pin "3") (pinfunction "2_3") (pintype "passive"))
      (node (ref "X8") (pin "4") (pinfunction "2_4") (pintype "passive"))
      (node (ref "X8") (pin "5") (pinfunction "2_5") (pintype "passive"))
      (node (ref "X9") (pin "2") (pinfunction "2_2") (pintype "passive"))
      (node (ref "X9") (pin "3") (pinfunction "2_3") (pintype "passive"))
      (node (ref "X9") (pin "4") (pinfunction "2_4") (pintype "passive"))
      (node (ref "X9") (pin "5") (pinfunction "2_5") (pintype "passive"))
    )
    (net (code "14") (name "GNSS{slash}PV") (class "Default")
      (node (ref "IC9") (pin "7") (pinfunction "PE2_7") (pintype "bidirectional"))
      (node (ref "SV2") (pin "22") (pinfunction "22_22") (pintype "passive"))
    )
    (net (code "15") (name "GNSS{slash}RXD") (class "Default")
      (node (ref "IC9") (pin "18") (pinfunction "PA1/U0TX_18") (pintype "bidirectional"))
      (node (ref "SV2") (pin "15") (pinfunction "15_15") (pintype "passive"))
    )
    (net (code "16") (name "GNSS{slash}TXD") (class "Default")
      (node (ref "IC9") (pin "17") (pinfunction "PA0/U0RX_17") (pintype "bidirectional"))
      (node (ref "SV2") (pin "16") (pinfunction "16_16") (pintype "passive"))
    )
    (net (code "17") (name "GNSS{slash}~{RESETIN}") (class "Default")
      (node (ref "IC9") (pin "6") (pinfunction "PE3_6") (pintype "bidirectional"))
      (node (ref "SV2") (pin "10") (pinfunction "10_10") (pintype "passive"))
    )
    (net (code "18") (name "GPIO1") (class "Default")
      (node (ref "IC9") (pin "16") (pinfunction "PC4_16") (pintype "bidirectional"))
      (node (ref "SV2") (pin "1") (pinfunction "1_1") (pintype "passive"))
    )
    (net (code "19") (name "GPIO2") (class "Default")
      (node (ref "IC9") (pin "43") (pinfunction "PD4_43") (pintype "bidirectional"))
      (node (ref "SV2") (pin "2") (pinfunction "2_2") (pintype "passive"))
    )
    (net (code "20") (name "GPIO3") (class "Default")
      (node (ref "IC9") (pin "44") (pinfunction "PD5_44") (pintype "bidirectional"))
      (node (ref "SV3") (pin "1") (pinfunction "1_1") (pintype "passive"))
    )
    (net (code "21") (name "GPIO4") (class "Default")
      (node (ref "IC9") (pin "45") (pinfunction "PB0/USB0ID_45") (pintype "bidirectional"))
      (node (ref "SV3") (pin "2") (pinfunction "2_2") (pintype "passive"))
    )
    (net (code "22") (name "GPIO5") (class "Default")
      (node (ref "IC9") (pin "15") (pinfunction "PC5_15") (pintype "bidirectional"))
      (node (ref "SV3") (pin "5") (pinfunction "5_5") (pintype "passive"))
    )
    (net (code "23") (name "Net-(C60-Pad2)") (class "Default")
      (node (ref "C60") (pin "2") (pinfunction "2_2") (pintype "passive"))
      (node (ref "X5") (pin "1") (pinfunction "1_1") (pintype "passive"))
    )
    (net (code "24") (name "Net-(C62-Pad1)") (class "Default")
      (node (ref "C62") (pin "1") (pinfunction "1_1") (pintype "passive"))
      (node (ref "C63") (pin "1") (pinfunction "1_1") (pintype "passive"))
      (node (ref "C64") (pin "1") (pinfunction "1_1") (pintype "passive"))
      (node (ref "C65") (pin "1") (pinfunction "1_1") (pintype "passive"))
      (node (ref "IC9") (pin "25") (pinfunction "VDDC_25") (pintype "bidirectional"))
      (node (ref "IC9") (pin "56") (pinfunction "VDDC_56") (pintype "bidirectional"))
    )
    (net (code "25") (name "Net-(C69-Pad1)") (class "Default")
      (node (ref "C69") (pin "1") (pinfunction "1_1") (pintype "passive"))
      (node (ref "X6") (pin "1") (pinfunction "1_1") (pintype "passive"))
    )
    (net (code "26") (name "Net-(C91-Pad1)") (class "Default")
      (node (ref "C91") (pin "1") (pinfunction "1_1") (pintype "passive"))
      (node (ref "X11") (pin "1") (pinfunction "1_1") (pintype "passive"))
    )
    (net (code "27") (name "Net-(C91-Pad2)") (class "Default")
      (node (ref "C91") (pin "2") (pinfunction "2_2") (pintype "passive"))
      (node (ref "IC15") (pin "RF_IN") (pinfunction "RF_IN_RF_IN") (pintype "bidirectional"))
    )
    (net (code "28") (name "Net-(FL1-IN)") (class "Default")
      (node (ref "FL1") (pin "B") (pinfunction "IN_B") (pintype "bidirectional"))
      (node (ref "X14") (pin "1") (pinfunction "1_1") (pintype "passive"))
    )
    (net (code "29") (name "Net-(FL1-OUT)") (class "Default")
      (node (ref "FL1") (pin "E") (pinfunction "OUT_E") (pintype "bidirectional"))
      (node (ref "X9") (pin "1") (pinfunction "1_1") (pintype "passive"))
    )
    (net (code "30") (name "Net-(FL2-RF_IN)") (class "Default")
      (node (ref "FL2") (pin "2") (pinfunction "RF_IN_2") (pintype "bidirectional"))
      (node (ref "X12") (pin "1") (pinfunction "1_1") (pintype "passive"))
    )
    (net (code "31") (name "Net-(FL2-RF_OUT)") (class "Default")
      (node (ref "FL2") (pin "6") (pinfunction "RF_OUT_6") (pintype "bidirectional"))
      (node (ref "X17") (pin "1") (pinfunction "1_1") (pintype "passive"))
    )
    (net (code "32") (name "Net-(FL3-RF_IN)") (class "Default")
      (node (ref "FL3") (pin "2") (pinfunction "RF_IN_2") (pintype "bidirectional"))
      (node (ref "X13") (pin "1") (pinfunction "1_1") (pintype "passive"))
    )
    (net (code "33") (name "Net-(FL3-RF_OUT)") (class "Default")
      (node (ref "FL3") (pin "6") (pinfunction "RF_OUT_6") (pintype "bidirectional"))
      (node (ref "X18") (pin "1") (pinfunction "1_1") (pintype "passive"))
    )
    (net (code "34") (name "Net-(IC1-IN)") (class "Default")
      (node (ref "C6") (pin "1") (pinfunction "1_1") (pintype "passive"))
      (node (ref "IC1") (pin "1") (pinfunction "IN_1") (pintype "power_in"))
      (node (ref "JP3") (pin "1") (pinfunction "1_1") (pintype "passive"))
      (node (ref "R1") (pin "2") (pinfunction "P$2_2") (pintype "passive"))
      (node (ref "R2") (pin "2") (pinfunction "P$2_2") (pintype "passive"))
    )
    (net (code "35") (name "Net-(IC1-NR)") (class "Default")
      (node (ref "C1") (pin "1") (pinfunction "1_1") (pintype "passive"))
      (node (ref "IC1") (pin "4") (pinfunction "NR_4") (pintype "input"))
    )
    (net (code "36") (name "Net-(IC1-OUT)") (class "Default")
      (node (ref "C13") (pin "1") (pinfunction "1_1") (pintype "passive"))
      (node (ref "C18") (pin "1") (pinfunction "1_1") (pintype "passive"))
      (node (ref "C19") (pin "2") (pinfunction "2_2") (pintype "passive"))
      (node (ref "C20") (pin "2") (pinfunction "2_2") (pintype "passive"))
      (node (ref "C27") (pin "2") (pinfunction "2_2") (pintype "passive"))
      (node (ref "C29") (pin "2") (pinfunction "2_2") (pintype "passive"))
      (node (ref "C3") (pin "1") (pinfunction "1_1") (pintype "passive"))
      (node (ref "C30") (pin "2") (pinfunction "2_2") (pintype "passive"))
      (node (ref "C33") (pin "2") (pinfunction "2_2") (pintype "passive"))
      (node (ref "C34") (pin "2") (pinfunction "2_2") (pintype "passive"))
      (node (ref "C36") (pin "2") (pinfunction "2_2") (pintype "passive"))
      (node (ref "C43") (pin "2") (pinfunction "2_2") (pintype "passive"))
      (node (ref "C44") (pin "2") (pinfunction "2_2") (pintype "passive"))
      (node (ref "C52") (pin "2") (pinfunction "2_2") (pintype "passive"))
      (node (ref "IC1") (pin "5") (pinfunction "OUT_5") (pintype "output"))
      (node (ref "IC5") (pin "2") (pinfunction "VCCA_2") (pintype "bidirectional"))
      (node (ref "IC8") (pin "1") (pinfunction "VDD_GUARD_1") (pintype "bidirectional"))
      (node (ref "IC8") (pin "12") (pinfunction "DVDD_2_12") (pintype "bidirectional"))
      (node (ref "IC8") (pin "13") (pinfunction "AVDD_IF_13") (pintype "bidirectional"))
      (node (ref "IC8") (pin "15") (pinfunction "AVDD_RF_15") (pintype "bidirectional"))
      (node (ref "IC8") (pin "22") (pinfunction "AVDD_SYNTH_1_22") (pintype "bidirectional"))
      (node (ref "IC8") (pin "25") (pinfunction "AVDD_PFD_CHP_25") (pintype "bidirectional"))
      (node (ref "IC8") (pin "26") (pinfunction "DCPL_PFD_CHIP_26") (pintype "bidirectional"))
      (node (ref "IC8") (pin "27") (pinfunction "AVDD_SYNTH2_27") (pintype "bidirectional"))
      (node (ref "IC8") (pin "28") (pinfunction "AVDD_XOSC_28") (pintype "bidirectional"))
      (node (ref "IC8") (pin "29") (pinfunction "DCPL_XOSC_29") (pintype "bidirectional"))
      (node (ref "IC8") (pin "5") (pinfunction "DVDD_1_5") (pintype "bidirectional"))
      (node (ref "JP7") (pin "1") (pinfunction "1_1") (pintype "passive"))
      (node (ref "LED2") (pin "A") (pinfunction "A_A") (pintype "passive"))
      (node (ref "Q2") (pin "2") (pinfunction "S_2") (pintype "passive"))
      (node (ref "R10") (pin "2") (pinfunction "P$2_2") (pintype "passive"))
      (node (ref "R17") (pin "2") (pinfunction "P$2_2") (pintype "passive"))
      (node (ref "R9") (pin "2") (pinfunction "P$2_2") (pintype "passive"))
      (node (ref "X4") (pin "6") (pinfunction "VCC_6") (pintype "power_in"))
    )
    (net (code "37") (name "Net-(IC2-IN)") (class "Default")
      (node (ref "C7") (pin "1") (pinfunction "1_1") (pintype "passive"))
      (node (ref "IC2") (pin "1") (pinfunction "IN_1") (pintype "power_in"))
      (node (ref "JP2") (pin "2") (pinfunction "2_2") (pintype "passive"))
      (node (ref "R3") (pin "2") (pinfunction "P$2_2") (pintype "passive"))
      (node (ref "R4") (pin "2") (pinfunction "P$2_2") (pintype "passive"))
    )
    (net (code "38") (name "Net-(IC2-NR)") (class "Default")
      (node (ref "C2") (pin "1") (pinfunction "1_1") (pintype "passive"))
      (node (ref "IC2") (pin "4") (pinfunction "NR_4") (pintype "input"))
    )
    (net (code "39") (name "Net-(IC2-OUT)") (class "Default")
      (node (ref "C12") (pin "1") (pinfunction "1_1") (pintype "passive"))
      (node (ref "C14") (pin "1") (pinfunction "1_1") (pintype "passive"))
      (node (ref "C15") (pin "2") (pinfunction "2_2") (pintype "passive"))
      (node (ref "C16") (pin "2") (pinfunction "2_2") (pintype "passive"))
      (node (ref "C23") (pin "2") (pinfunction "2_2") (pintype "passive"))
      (node (ref "C25") (pin "2") (pinfunction "2_2") (pintype "passive"))
      (node (ref "C26") (pin "2") (pinfunction "2_2") (pintype "passive"))
      (node (ref "C28") (pin "2") (pinfunction "2_2") (pintype "passive"))
      (node (ref "C31") (pin "2") (pinfunction "2_2") (pintype "passive"))
      (node (ref "C32") (pin "2") (pinfunction "2_2") (pintype "passive"))
      (node (ref "C35") (pin "2") (pinfunction "2_2") (pintype "passive"))
      (node (ref "C37") (pin "1") (pinfunction "1_1") (pintype "passive"))
      (node (ref "C4") (pin "1") (pinfunction "1_1") (pintype "passive"))
      (node (ref "C40") (pin "2") (pinfunction "2_2") (pintype "passive"))
      (node (ref "C46") (pin "2") (pinfunction "2_2") (pintype "passive"))
      (node (ref "C48") (pin "1") (pinfunction "1_1") (pintype "passive"))
      (node (ref "C49") (pin "1") (pinfunction "1_1") (pintype "passive"))
      (node (ref "C5") (pin "1") (pinfunction "1_1") (pintype "passive"))
      (node (ref "C9") (pin "1") (pinfunction "1_1") (pintype "passive"))
      (node (ref "C93") (pin "1") (pinfunction "1_1") (pintype "passive"))
      (node (ref "IC2") (pin "5") (pinfunction "OUT_5") (pintype "output"))
      (node (ref "IC3") (pin "5") (pinfunction "VCC_5") (pintype "bidirectional"))
      (node (ref "IC6") (pin "2") (pinfunction "VCCA_2") (pintype "bidirectional"))
      (node (ref "IC7") (pin "1") (pinfunction "VDD_GUARD_1") (pintype "bidirectional"))
      (node (ref "IC7") (pin "12") (pinfunction "DVDD_2_12") (pintype "bidirectional"))
      (node (ref "IC7") (pin "13") (pinfunction "AVDD_IF_13") (pintype "bidirectional"))
      (node (ref "IC7") (pin "15") (pinfunction "AVDD_RF_15") (pintype "bidirectional"))
      (node (ref "IC7") (pin "22") (pinfunction "AVDD_SYNTH_1_22") (pintype "bidirectional"))
      (node (ref "IC7") (pin "25") (pinfunction "AVDD_PFD_CHP_25") (pintype "bidirectional"))
      (node (ref "IC7") (pin "26") (pinfunction "DCPL_PFD_CHIP_26") (pintype "bidirectional"))
      (node (ref "IC7") (pin "27") (pinfunction "AVDD_SYNTH2_27") (pintype "bidirectional"))
      (node (ref "IC7") (pin "28") (pinfunction "AVDD_XOSC_28") (pintype "bidirectional"))
      (node (ref "IC7") (pin "29") (pinfunction "DCPL_XOSC_29") (pintype "bidirectional"))
      (node (ref "IC7") (pin "5") (pinfunction "DVDD_1_5") (pintype "bidirectional"))
      (node (ref "IC77") (pin "5") (pinfunction "+V_5") (pintype "power_in"))
      (node (ref "JP1") (pin "1") (pinfunction "1_1") (pintype "passive"))
      (node (ref "LED1") (pin "A") (pinfunction "A_A") (pintype "passive"))
      (node (ref "R13") (pin "2") (pinfunction "P$2_2") (pintype "passive"))
      (node (ref "R7") (pin "2") (pinfunction "P$2_2") (pintype "passive"))
      (node (ref "R8") (pin "2") (pinfunction "P$2_2") (pintype "passive"))
      (node (ref "X3") (pin "6") (pinfunction "VCC_6") (pintype "power_in"))
    )
    (net (code "40") (name "Net-(IC3-P1.6)") (class "Default")
      (node (ref "IC3") (pin "11") (pinfunction "P1.6_11") (pintype "bidirectional"))
      (node (ref "TP24") (pin "TP") (pinfunction "TP_TP") (pintype "input"))
    )
    (net (code "41") (name "Net-(IC3-P1.7)") (class "Default")
      (node (ref "IC3") (pin "10") (pinfunction "P1.7_10") (pintype "bidirectional"))
      (node (ref "TP23") (pin "TP") (pinfunction "TP_TP") (pintype "input"))
    )
    (net (code "42") (name "Net-(IC3-P2.0)") (class "Default")
      (node (ref "IC3") (pin "9") (pinfunction "P2.0_9") (pintype "bidirectional"))
      (node (ref "R16") (pin "2") (pinfunction "P$2_2") (pintype "passive"))
    )
    (net (code "43") (name "Net-(IC3-TEST)") (class "Default")
      (node (ref "IC3") (pin "3") (pinfunction "TEST_3") (pintype "bidirectional"))
      (node (ref "JP1") (pin "3") (pinfunction "3_3") (pintype "passive"))
    )
    (net (code "44") (name "Net-(IC3-~{RST})") (class "Default")
      (node (ref "IC3") (pin "4") (pinfunction "~{RST}_4") (pintype "bidirectional"))
      (node (ref "JP1") (pin "4") (pinfunction "4_4") (pintype "passive"))
    )
    (net (code "45") (name "Net-(IC4-OUT)") (class "Default")
      (node (ref "C11") (pin "1") (pinfunction "1_1") (pintype "passive"))
      (node (ref "IC4") (pin "2") (pinfunction "OUT_2") (pintype "passive"))
      (node (ref "JP4") (pin "1") (pinfunction "1_1") (pintype "passive"))
    )
    (net (code "46") (name "Net-(IC5-OE)") (class "Default")
      (node (ref "IC5") (pin "10") (pinfunction "OE_10") (pintype "bidirectional"))
      (node (ref "JP6") (pin "1") (pinfunction "1_1") (pintype "passive"))
      (node (ref "R9") (pin "1") (pinfunction "P$1_1") (pintype "passive"))
    )
    (net (code "47") (name "Net-(IC6-OE)") (class "Default")
      (node (ref "IC6") (pin "10") (pinfunction "OE_10") (pintype "bidirectional"))
      (node (ref "JP5") (pin "1") (pinfunction "1_1") (pintype "passive"))
      (node (ref "R8") (pin "1") (pinfunction "P$1_1") (pintype "passive"))
    )
    (net (code "48") (name "Net-(IC7-DCPL)") (class "Default")
      (node (ref "C17") (pin "1") (pinfunction "1_1") (pintype "passive"))
      (node (ref "IC7") (pin "6") (pinfunction "DCPL_6") (pintype "bidirectional"))
    )
    (net (code "49") (name "Net-(IC7-DCPL_VCO)") (class "Default")
      (node (ref "C53") (pin "1") (pinfunction "1_1") (pintype "passive"))
      (node (ref "IC7") (pin "21") (pinfunction "DCPL_VCO_21") (pintype "bidirectional"))
    )
    (net (code "50") (name "Net-(IC7-EXT_XOSC)") (class "Default")
      (node (ref "C22") (pin "2") (pinfunction "2_2") (pintype "passive"))
      (node (ref "IC7") (pin "32") (pinfunction "EXT_XOSC_32") (pintype "bidirectional"))
    )
    (net (code "51") (name "Net-(IC7-LPF0)") (class "Default")
      (node (ref "C41") (pin "1") (pinfunction "1_1") (pintype "passive"))
      (node (ref "IC7") (pin "23") (pinfunction "LPF0_23") (pintype "bidirectional"))
    )
    (net (code "52") (name "Net-(IC7-LPF1)") (class "Default")
      (node (ref "C41") (pin "2") (pinfunction "2_2") (pintype "passive"))
      (node (ref "IC7") (pin "24") (pinfunction "LPF1_24") (pintype "bidirectional"))
    )
    (net (code "53") (name "Net-(IC7-PA)") (class "Default")
      (node (ref "C42") (pin "1") (pinfunction "1_1") (pintype "passive"))
      (node (ref "IC7") (pin "17") (pinfunction "PA_17") (pintype "bidirectional"))
      (node (ref "L1") (pin "1") (pinfunction "P$1_1") (pintype "passive"))
    )
    (net (code "54") (name "Net-(IC7-RBIAS)") (class "Default")
      (node (ref "IC7") (pin "14") (pinfunction "RBIAS_14") (pintype "bidirectional"))
      (node (ref "R11") (pin "1") (pinfunction "P$1_1") (pintype "passive"))
    )
    (net (code "55") (name "Net-(IC7-TRX_SW)") (class "Default")
      (node (ref "IC7") (pin "18") (pinfunction "TRX_SW_18") (pintype "bidirectional"))
      (node (ref "TP3") (pin "TP") (pinfunction "TP_TP") (pintype "input"))
    )
    (net (code "56") (name "Net-(IC8-DCPL)") (class "Default")
      (node (ref "C21") (pin "1") (pinfunction "1_1") (pintype "passive"))
      (node (ref "IC8") (pin "6") (pinfunction "DCPL_6") (pintype "bidirectional"))
    )
    (net (code "57") (name "Net-(IC8-DCPL_VCO)") (class "Default")
      (node (ref "C55") (pin "1") (pinfunction "1_1") (pintype "passive"))
      (node (ref "IC8") (pin "21") (pinfunction "DCPL_VCO_21") (pintype "bidirectional"))
    )
    (net (code "58") (name "Net-(IC8-EXT_XOSC)") (class "Default")
      (node (ref "C24") (pin "2") (pinfunction "2_2") (pintype "passive"))
      (node (ref "IC8") (pin "32") (pinfunction "EXT_XOSC_32") (pintype "bidirectional"))
    )
    (net (code "59") (name "Net-(IC8-LNA_N)") (class "Default")
      (node (ref "C57") (pin "1") (pinfunction "1_1") (pintype "passive"))
      (node (ref "IC8") (pin "20") (pinfunction "LNA_N_20") (pintype "bidirectional"))
      (node (ref "L3") (pin "1") (pinfunction "P$1_1") (pintype "passive"))
      (node (ref "L6") (pin "2") (pinfunction "P$2_2") (pintype "passive"))
    )
    (net (code "60") (name "Net-(IC8-LNA_P)") (class "Default")
      (node (ref "C58") (pin "1") (pinfunction "1_1") (pintype "passive"))
      (node (ref "IC8") (pin "19") (pinfunction "LNA_P_19") (pintype "bidirectional"))
      (node (ref "L3") (pin "2") (pinfunction "P$2_2") (pintype "passive"))
      (node (ref "L7") (pin "1") (pinfunction "P$1_1") (pintype "passive"))
    )
    (net (code "61") (name "Net-(IC8-LPF0)") (class "Default")
      (node (ref "C45") (pin "1") (pinfunction "1_1") (pintype "passive"))
      (node (ref "IC8") (pin "23") (pinfunction "LPF0_23") (pintype "bidirectional"))
    )
    (net (code "62") (name "Net-(IC8-LPF1)") (class "Default")
      (node (ref "C45") (pin "2") (pinfunction "2_2") (pintype "passive"))
      (node (ref "IC8") (pin "24") (pinfunction "LPF1_24") (pintype "bidirectional"))
    )
    (net (code "63") (name "Net-(IC8-RBIAS)") (class "Default")
      (node (ref "IC8") (pin "14") (pinfunction "RBIAS_14") (pintype "bidirectional"))
      (node (ref "R12") (pin "1") (pinfunction "P$1_1") (pintype "passive"))
    )
    (net (code "64") (name "Net-(IC9-OSC0)") (class "Default")
      (node (ref "C77") (pin "1") (pinfunction "1_1") (pintype "passive"))
      (node (ref "IC9") (pin "40") (pinfunction "OSC0_40") (pintype "bidirectional"))
      (node (ref "Y1") (pin "1") (pinfunction "1_1") (pintype "passive"))
    )
    (net (code "65") (name "Net-(IC9-OSC1)") (class "Default")
      (node (ref "C76") (pin "1") (pinfunction "1_1") (pintype "passive"))
      (node (ref "IC9") (pin "41") (pinfunction "OSC1_41") (pintype "bidirectional"))
      (node (ref "Y1") (pin "3") (pinfunction "2_3") (pintype "passive"))
    )
    (net (code "66") (name "Net-(IC9-PB1{slash}USB0VBUS)") (class "Default")
      (node (ref "IC9") (pin "46") (pinfunction "PB1/USB0VBUS_46") (pintype "bidirectional"))
      (node (ref "R30") (pin "2") (pinfunction "P$2_2") (pintype "passive"))
    )
    (net (code "67") (name "Net-(IC9-PC2{slash}TDI)") (class "Default")
      (node (ref "IC9") (pin "50") (pinfunction "PC2/TDI_50") (pintype "bidirectional"))
      (node (ref "R31") (pin "2") (pinfunction "P$2_2") (pintype "passive"))
    )
    (net (code "68") (name "Net-(IC9-XOSC0)") (class "Default")
      (node (ref "C75") (pin "1") (pinfunction "1_1") (pintype "passive"))
      (node (ref "IC9") (pin "34") (pinfunction "XOSC0_34") (pintype "bidirectional"))
      (node (ref "Q3") (pin "P$2") (pinfunction "2_P$2") (pintype "bidirectional"))
    )
    (net (code "69") (name "Net-(IC9-XOSC1)") (class "Default")
      (node (ref "C74") (pin "1") (pinfunction "1_1") (pintype "passive"))
      (node (ref "IC9") (pin "36") (pinfunction "XOSC1_36") (pintype "bidirectional"))
      (node (ref "Q3") (pin "P$1") (pinfunction "1_P$1") (pintype "bidirectional"))
    )
    (net (code "70") (name "Net-(IC9-~{WAKE})") (class "Default")
      (node (ref "IC9") (pin "32") (pinfunction "~{WAKE}_32") (pintype "bidirectional"))
      (node (ref "R14") (pin "1") (pinfunction "P$1_1") (pintype "passive"))
    )
    (net (code "71") (name "Net-(IC10-RF_IN)") (class "Default")
      (node (ref "C70") (pin "1") (pinfunction "1_1") (pintype "passive"))
      (node (ref "IC10") (pin "3") (pinfunction "RF_IN_3") (pintype "input"))
    )
    (net (code "72") (name "Net-(IC10-RF_OUT)") (class "Default")
      (node (ref "C69") (pin "2") (pinfunction "2_2") (pintype "passive"))
      (node (ref "IC10") (pin "1") (pinfunction "RF_OUT_1") (pintype "output"))
      (node (ref "L9") (pin "1") (pinfunction "P$1_1") (pintype "passive"))
    )
    (net (code "73") (name "Net-(IC11-REGOUT)") (class "Default")
      (node (ref "C80") (pin "1") (pinfunction "1_1") (pintype "passive"))
      (node (ref "IC11") (pin "10") (pinfunction "REGOUT_10") (pintype "bidirectional"))
    )
    (net (code "74") (name "Net-(IC12-B3)") (class "Default")
      (node (ref "IC12") (pin "17") (pinfunction "B3_17") (pintype "bidirectional"))
      (node (ref "JP12") (pin "3") (pinfunction "3_3") (pintype "passive"))
    )
    (net (code "75") (name "Net-(IC12-B4)") (class "Default")
      (node (ref "IC12") (pin "16") (pinfunction "B4_16") (pintype "bidirectional"))
      (node (ref "JP12") (pin "2") (pinfunction "2_2") (pintype "passive"))
    )
    (net (code "76") (name "Net-(IC17-IN)") (class "Default")
      (node (ref "C100") (pin "1") (pinfunction "1_1") (pintype "passive"))
      (node (ref "IC17") (pin "3") (pinfunction "IN_3") (pintype "input"))
      (node (ref "L17") (pin "2") (pinfunction "P$2_2") (pintype "passive"))
    )
    (net (code "77") (name "Net-(IC17-VBA1)") (class "Default")
      (node (ref "IC17") (pin "1") (pinfunction "VBA1_1") (pintype "input"))
      (node (ref "R27") (pin "2") (pinfunction "P$2_2") (pintype "passive"))
    )
    (net (code "78") (name "Net-(IC17-VBA2)") (class "Default")
      (node (ref "IC17") (pin "12") (pinfunction "VBA2_12") (pintype "input"))
      (node (ref "R26") (pin "2") (pinfunction "P$2_2") (pintype "passive"))
    )
    (net (code "79") (name "Net-(IC17-VBIAS)") (class "Default")
      (node (ref "C103") (pin "1") (pinfunction "1_1") (pintype "passive"))
      (node (ref "C104") (pin "1") (pinfunction "1_1") (pintype "passive"))
      (node (ref "C106") (pin "1") (pinfunction "1_1") (pintype "passive"))
      (node (ref "C94") (pin "1") (pinfunction "1_1") (pintype "passive"))
      (node (ref "C95") (pin "1") (pinfunction "1_1") (pintype "passive"))
      (node (ref "C96") (pin "1") (pinfunction "1_1") (pintype "passive"))
      (node (ref "C99") (pin "1") (pinfunction "1_1") (pintype "passive"))
      (node (ref "IC17") (pin "2") (pinfunction "VBIAS_2") (pintype "input"))
      (node (ref "JP11") (pin "1") (pinfunction "1_1") (pintype "passive"))
      (node (ref "L14") (pin "2") (pinfunction "P$2_2") (pintype "passive"))
      (node (ref "L18") (pin "2") (pinfunction "P$2_2") (pintype "passive"))
      (node (ref "LED9") (pin "A") (pinfunction "A_A") (pintype "passive"))
      (node (ref "R26") (pin "1") (pinfunction "P$1_1") (pintype "passive"))
      (node (ref "R27") (pin "1") (pinfunction "P$1_1") (pintype "passive"))
    )
    (net (code "80") (name "Net-(IC17-VCC1)") (class "Default")
      (node (ref "C97") (pin "1") (pinfunction "1_1") (pintype "passive"))
      (node (ref "IC17") (pin "11") (pinfunction "VCC1_11") (pintype "passive"))
      (node (ref "L14") (pin "1") (pinfunction "P$1_1") (pintype "passive"))
    )
    (net (code "81") (name "Net-(IC77-Y)") (class "Default")
      (node (ref "IC77") (pin "4") (pinfunction "Y_4") (pintype "output"))
      (node (ref "Q4") (pin "1") (pinfunction "G_1") (pintype "passive"))
      (node (ref "R25") (pin "2") (pinfunction "P$2_2") (pintype "passive"))
    )
    (net (code "82") (name "Net-(L1-P$2)") (class "Default")
      (node (ref "C37") (pin "2") (pinfunction "2_2") (pintype "passive"))
      (node (ref "L1") (pin "2") (pinfunction "P$2_2") (pintype "passive"))
      (node (ref "R13") (pin "1") (pinfunction "P$1_1") (pintype "passive"))
    )
    (net (code "83") (name "Net-(L2-P$1)") (class "Default")
      (node (ref "C42") (pin "2") (pinfunction "2_2") (pintype "passive"))
      (node (ref "C47") (pin "1") (pinfunction "1_1") (pintype "passive"))
      (node (ref "L2") (pin "1") (pinfunction "P$1_1") (pintype "passive"))
    )
    (net (code "84") (name "Net-(L2-P$2)") (class "Default")
      (node (ref "C47") (pin "2") (pinfunction "2_2") (pintype "passive"))
      (node (ref "C50") (pin "2") (pinfunction "2_2") (pintype "passive"))
      (node (ref "L2") (pin "2") (pinfunction "P$2_2") (pintype "passive"))
      (node (ref "L4") (pin "1") (pinfunction "P$1_1") (pintype "passive"))
    )
    (net (code "85") (name "Net-(L4-P$2)") (class "Default")
      (node (ref "C56") (pin "2") (pinfunction "2_2") (pintype "passive"))
      (node (ref "C59") (pin "1") (pinfunction "1_1") (pintype "passive"))
      (node (ref "L4") (pin "2") (pinfunction "P$2_2") (pintype "passive"))
      (node (ref "L5") (pin "1") (pinfunction "P$1_1") (pintype "passive"))
    )
    (net (code "86") (name "Net-(L5-P$2)") (class "Default")
      (node (ref "C59") (pin "2") (pinfunction "2_2") (pintype "passive"))
      (node (ref "L5") (pin "2") (pinfunction "P$2_2") (pintype "passive"))
      (node (ref "X8") (pin "1") (pinfunction "1_1") (pintype "passive"))
    )
    (net (code "87") (name "Net-(L7-P$2)") (class "Default")
      (node (ref "C57") (pin "2") (pinfunction "2_2") (pintype "passive"))
      (node (ref "L7") (pin "2") (pinfunction "P$2_2") (pintype "passive"))
      (node (ref "L8") (pin "1") (pinfunction "P$1_1") (pintype "passive"))
    )
    (net (code "88") (name "Net-(L8-P$2)") (class "Default")
      (node (ref "C60") (pin "1") (pinfunction "1_1") (pintype "passive"))
      (node (ref "L8") (pin "2") (pinfunction "P$2_2") (pintype "passive"))
    )
    (net (code "89") (name "Net-(L9-P$2)") (class "Default")
      (node (ref "C66") (pin "2") (pinfunction "2_2") (pintype "passive"))
      (node (ref "JP8") (pin "1") (pinfunction "1_1") (pintype "passive"))
      (node (ref "L9") (pin "2") (pinfunction "P$2_2") (pintype "passive"))
      (node (ref "LED3") (pin "A") (pinfunction "A_A") (pintype "passive"))
    )
    (net (code "90") (name "Net-(L10-P$2)") (class "Default")
      (node (ref "C70") (pin "2") (pinfunction "2_2") (pintype "passive"))
      (node (ref "C71") (pin "1") (pinfunction "1_1") (pintype "passive"))
      (node (ref "L10") (pin "2") (pinfunction "P$2_2") (pintype "passive"))
    )
    (net (code "91") (name "Net-(L11-P$2)") (class "Default")
      (node (ref "C71") (pin "2") (pinfunction "2_2") (pintype "passive"))
      (node (ref "L11") (pin "2") (pinfunction "P$2_2") (pintype "passive"))
      (node (ref "X7") (pin "1") (pinfunction "1_1") (pintype "passive"))
    )
    (net (code "92") (name "Net-(L12-P$1)") (class "Default")
      (node (ref "C90") (pin "1") (pinfunction "1_1") (pintype "passive"))
      (node (ref "IC15") (pin "RF_OUT") (pinfunction "RF_OUT_RF_OUT") (pintype "bidirectional"))
      (node (ref "L12") (pin "1") (pinfunction "P$1_1") (pintype "passive"))
    )
    (net (code "93") (name "Net-(L12-P$2)") (class "Default")
      (node (ref "C84") (pin "1") (pinfunction "1_1") (pintype "passive"))
      (node (ref "C85") (pin "1") (pinfunction "1_1") (pintype "passive"))
      (node (ref "C86") (pin "2") (pinfunction "2_2") (pintype "passive"))
      (node (ref "JP9") (pin "1") (pinfunction "1_1") (pintype "passive"))
      (node (ref "L12") (pin "2") (pinfunction "P$2_2") (pintype "passive"))
      (node (ref "LED4") (pin "A") (pinfunction "A_A") (pintype "passive"))
    )
    (net (code "94") (name "Net-(L13-P$1)") (class "Default")
      (node (ref "C88") (pin "2") (pinfunction "2_2") (pintype "passive"))
      (node (ref "C90") (pin "2") (pinfunction "2_2") (pintype "passive"))
      (node (ref "L13") (pin "1") (pinfunction "P$1_1") (pintype "passive"))
    )
    (net (code "95") (name "Net-(L13-P$2)") (class "Default")
      (node (ref "C89") (pin "2") (pinfunction "2_2") (pintype "passive"))
      (node (ref "L13") (pin "2") (pinfunction "P$2_2") (pintype "passive"))
      (node (ref "X10") (pin "1") (pinfunction "1_1") (pintype "passive"))
    )
    (net (code "96") (name "Net-(L15-P$2)") (class "Default")
      (node (ref "C102") (pin "1") (pinfunction "1_1") (pintype "passive"))
      (node (ref "L15") (pin "2") (pinfunction "P$2_2") (pintype "passive"))
      (node (ref "L16") (pin "1") (pinfunction "P$1_1") (pintype "passive"))
    )
    (net (code "97") (name "Net-(L16-P$2)") (class "Default")
      (node (ref "C98") (pin "1") (pinfunction "1_1") (pintype "passive"))
      (node (ref "L16") (pin "2") (pinfunction "P$2_2") (pintype "passive"))
      (node (ref "X15") (pin "1") (pinfunction "1_1") (pintype "passive"))
    )
    (net (code "98") (name "Net-(L17-P$1)") (class "Default")
      (node (ref "C101") (pin "1") (pinfunction "1_1") (pintype "passive"))
      (node (ref "L17") (pin "1") (pinfunction "P$1_1") (pintype "passive"))
      (node (ref "X16") (pin "1") (pinfunction "1_1") (pintype "passive"))
    )
    (net (code "99") (name "Net-(L18-P$1)") (class "Default")
      (node (ref "C102") (pin "2") (pinfunction "2_2") (pintype "passive"))
      (node (ref "IC17") (pin "7") (pinfunction "OUT_7") (pintype "passive"))
      (node (ref "IC17") (pin "8") (pinfunction "OUT_8") (pintype "passive"))
      (node (ref "IC17") (pin "9") (pinfunction "OUT_9") (pintype "passive"))
      (node (ref "L18") (pin "1") (pinfunction "P$1_1") (pintype "passive"))
    )
    (net (code "100") (name "Net-(Q2-D)") (class "Default")
      (node (ref "JP7") (pin "2") (pinfunction "2_2") (pintype "passive"))
      (node (ref "JP8") (pin "2") (pinfunction "2_2") (pintype "passive"))
      (node (ref "Q2") (pin "3") (pinfunction "D_3") (pintype "passive"))
    )
    (net (code "101") (name "Net-(Q4-D)") (class "Default")
      (node (ref "Q4") (pin "3") (pinfunction "D_3") (pintype "passive"))
      (node (ref "Q5") (pin "1") (pinfunction "G_1") (pintype "passive"))
      (node (ref "R22") (pin "1") (pinfunction "P$1_1") (pintype "passive"))
    )
    (net (code "102") (name "Net-(R5-P$1)") (class "Default")
      (node (ref "LED2") (pin "C") (pinfunction "C_C") (pintype "passive"))
      (node (ref "R5") (pin "1") (pinfunction "P$1_1") (pintype "passive"))
    )
    (net (code "103") (name "Net-(R6-P$1)") (class "Default")
      (node (ref "LED1") (pin "C") (pinfunction "C_C") (pintype "passive"))
      (node (ref "R6") (pin "1") (pinfunction "P$1_1") (pintype "passive"))
    )
    (net (code "104") (name "Net-(R18-P$1)") (class "Default")
      (node (ref "LED3") (pin "C") (pinfunction "C_C") (pintype "passive"))
      (node (ref "R18") (pin "1") (pinfunction "P$1_1") (pintype "passive"))
    )
    (net (code "105") (name "Net-(R19-P$1)") (class "Default")
      (node (ref "LED4") (pin "C") (pinfunction "C_C") (pintype "passive"))
      (node (ref "R19") (pin "1") (pinfunction "P$1_1") (pintype "passive"))
    )
    (net (code "106") (name "Net-(R28-P$2)") (class "Default")
      (node (ref "LED5") (pin "C") (pinfunction "C_C") (pintype "passive"))
      (node (ref "R28") (pin "2") (pinfunction "P$2_2") (pintype "passive"))
    )
    (net (code "107") (name "Net-(R29-P$2)") (class "Default")
      (node (ref "LED6") (pin "C") (pinfunction "C_C") (pintype "passive"))
      (node (ref "R29") (pin "2") (pinfunction "P$2_2") (pintype "passive"))
    )
    (net (code "108") (name "Net-(R30-P$1)") (class "Default")
      (node (ref "LED7") (pin "A") (pinfunction "A_A") (pintype "passive"))
      (node (ref "R30") (pin "1") (pinfunction "P$1_1") (pintype "passive"))
    )
    (net (code "109") (name "Net-(R31-P$1)") (class "Default")
      (node (ref "LED8") (pin "A") (pinfunction "A_A") (pintype "passive"))
      (node (ref "R31") (pin "1") (pinfunction "P$1_1") (pintype "passive"))
    )
    (net (code "110") (name "Net-(R32-P$1)") (class "Default")
      (node (ref "LED9") (pin "C") (pinfunction "C_C") (pintype "passive"))
      (node (ref "R32") (pin "1") (pinfunction "P$1_1") (pintype "passive"))
    )
    (net (code "111") (name "Net-(X3-OUT)") (class "Default")
      (node (ref "C22") (pin "1") (pinfunction "1_1") (pintype "passive"))
      (node (ref "X3") (pin "4") (pinfunction "OUT_4") (pintype "output"))
    )
    (net (code "112") (name "Net-(X4-OUT)") (class "Default")
      (node (ref "C24") (pin "1") (pinfunction "1_1") (pintype "passive"))
      (node (ref "X4") (pin "4") (pinfunction "OUT_4") (pintype "output"))
    )
    (net (code "113") (name "PA_POWER") (class "Default")
      (node (ref "C61") (pin "1") (pinfunction "1_1") (pintype "passive"))
      (node (ref "IC17") (pin "6") (pinfunction "PDET_6") (pintype "output"))
      (node (ref "IC9") (pin "61") (pinfunction "PD0_61") (pintype "bidirectional"))
      (node (ref "TP16") (pin "TP") (pinfunction "TP_TP") (pintype "input"))
    )
    (net (code "114") (name "PA_PWR") (class "Default")
      (node (ref "JP10") (pin "2") (pinfunction "2_2") (pintype "passive"))
      (node (ref "JP11") (pin "2") (pinfunction "2_2") (pintype "passive"))
      (node (ref "JP9") (pin "2") (pinfunction "2_2") (pintype "passive"))
      (node (ref "Q5") (pin "3") (pinfunction "D_3") (pintype "passive"))
      (node (ref "R16") (pin "1") (pinfunction "P$1_1") (pintype "passive"))
    )
    (net (code "115") (name "PWR{slash}INT") (class "Default")
      (node (ref "IC9") (pin "10") (pinfunction "PD7_10") (pintype "bidirectional"))
      (node (ref "SV3") (pin "47") (pinfunction "47_47") (pintype "passive"))
    )
    (net (code "116") (name "PWR{slash}RXD") (class "Default")
      (node (ref "IC9") (pin "8") (pinfunction "PE1_8") (pintype "bidirectional"))
      (node (ref "SV2") (pin "47") (pinfunction "47_47") (pintype "passive"))
    )
    (net (code "117") (name "PWR{slash}TXD") (class "Default")
      (node (ref "IC9") (pin "9") (pinfunction "PE0_9") (pintype "bidirectional"))
      (node (ref "SV2") (pin "48") (pinfunction "48_48") (pintype "passive"))
    )
    (net (code "118") (name "RX_CLK") (class "Default")
      (node (ref "IC5") (pin "7") (pinfunction "A6_7") (pintype "bidirectional"))
      (node (ref "IC8") (pin "8") (pinfunction "SCK_8") (pintype "bidirectional"))
      (node (ref "TP19") (pin "TP") (pinfunction "TP_TP") (pintype "input"))
    )
    (net (code "119") (name "RX_CS") (class "Default")
      (node (ref "IC5") (pin "8") (pinfunction "A7_8") (pintype "bidirectional"))
      (node (ref "IC8") (pin "11") (pinfunction "CSN_11") (pintype "bidirectional"))
      (node (ref "TP22") (pin "TP") (pinfunction "TP_TP") (pintype "input"))
    )
    (net (code "120") (name "RX_GPIO0") (class "Default")
      (node (ref "IC5") (pin "1") (pinfunction "A1_1") (pintype "bidirectional"))
      (node (ref "IC8") (pin "10") (pinfunction "GPIO0_10") (pintype "bidirectional"))
      (node (ref "TP21") (pin "TP") (pinfunction "TP_TP") (pintype "input"))
    )
    (net (code "121") (name "RX_GPIO2") (class "Default")
      (node (ref "IC8") (pin "4") (pinfunction "GPIO2_4") (pintype "bidirectional"))
    )
    (net (code "122") (name "RX_GPIO3") (class "Default")
      (node (ref "IC8") (pin "3") (pinfunction "GPIO3_3") (pintype "bidirectional"))
      (node (ref "Q2") (pin "1") (pinfunction "G_1") (pintype "passive"))
      (node (ref "R17") (pin "1") (pinfunction "P$1_1") (pintype "passive"))
      (node (ref "TP5") (pin "TP") (pinfunction "TP_TP") (pintype "input"))
    )
    (net (code "123") (name "RX_MISO") (class "Default")
      (node (ref "IC5") (pin "6") (pinfunction "A5_6") (pintype "bidirectional"))
      (node (ref "IC8") (pin "9") (pinfunction "MISO_9") (pintype "bidirectional"))
      (node (ref "TP20") (pin "TP") (pinfunction "TP_TP") (pintype "input"))
    )
    (net (code "124") (name "RX_MOSI") (class "Default")
      (node (ref "IC5") (pin "5") (pinfunction "A4_5") (pintype "bidirectional"))
      (node (ref "IC8") (pin "7") (pinfunction "MOSI_7") (pintype "bidirectional"))
      (node (ref "TP18") (pin "TP") (pinfunction "TP_TP") (pintype "input"))
    )
    (net (code "125") (name "RX_REG_EN") (class "Default")
      (node (ref "IC1") (pin "3") (pinfunction "EN_3") (pintype "input"))
      (node (ref "IC9") (pin "23") (pinfunction "PA6_23") (pintype "bidirectional"))
      (node (ref "R2") (pin "1") (pinfunction "P$1_1") (pintype "passive"))
    )
    (net (code "126") (name "RX_RST") (class "Default")
      (node (ref "IC5") (pin "9") (pinfunction "A8_9") (pintype "bidirectional"))
      (node (ref "IC8") (pin "2") (pinfunction "NRESET_2") (pintype "bidirectional"))
      (node (ref "R10") (pin "1") (pinfunction "P$1_1") (pintype "passive"))
      (node (ref "TP17") (pin "TP") (pinfunction "TP_TP") (pintype "input"))
    )
    (net (code "127") (name "RX{slash}GPIO0") (class "Default")
      (node (ref "IC5") (pin "20") (pinfunction "B1_20") (pintype "bidirectional"))
      (node (ref "IC9") (pin "4") (pinfunction "PB7_4") (pintype "bidirectional"))
    )
    (net (code "128") (name "SWCLK") (class "Default")
      (node (ref "IC9") (pin "52") (pinfunction "PC0/TCK/SWCLK_52") (pintype "bidirectional"))
      (node (ref "J3") (pin "4") (pinfunction "SWCLK_4") (pintype "bidirectional"))
      (node (ref "SV2") (pin "3") (pinfunction "3_3") (pintype "passive"))
    )
    (net (code "129") (name "SWDIO") (class "Default")
      (node (ref "IC9") (pin "51") (pinfunction "PC1/TMS/SWDIO_51") (pintype "bidirectional"))
      (node (ref "J3") (pin "2") (pinfunction "SWDAT_2") (pintype "bidirectional"))
      (node (ref "SV2") (pin "4") (pinfunction "4_4") (pintype "passive"))
    )
    (net (code "130") (name "SWO") (class "Default")
      (node (ref "IC9") (pin "49") (pinfunction "PC3/TDO/SWO_49") (pintype "bidirectional"))
      (node (ref "J3") (pin "6") (pinfunction "SWO_6") (pintype "bidirectional"))
      (node (ref "SV3") (pin "3") (pinfunction "3_3") (pintype "passive"))
    )
    (net (code "131") (name "TC{slash}RX{slash}CS") (class "Default")
      (node (ref "IC5") (pin "13") (pinfunction "B7_13") (pintype "bidirectional"))
      (node (ref "IC9") (pin "20") (pinfunction "PA3/SSI0FSS_20") (pintype "bidirectional"))
    )
    (net (code "132") (name "TC{slash}TXRX{slash}CLK") (class "Default")
      (node (ref "IC5") (pin "14") (pinfunction "B6_14") (pintype "bidirectional"))
      (node (ref "IC6") (pin "14") (pinfunction "B6_14") (pintype "bidirectional"))
      (node (ref "IC9") (pin "30") (pinfunction "PF2_30") (pintype "bidirectional"))
    )
    (net (code "133") (name "TC{slash}TXRX{slash}MISO") (class "Default")
      (node (ref "IC5") (pin "15") (pinfunction "B5_15") (pintype "bidirectional"))
      (node (ref "IC6") (pin "15") (pinfunction "B5_15") (pintype "bidirectional"))
      (node (ref "IC9") (pin "28") (pinfunction "PF0_28") (pintype "bidirectional"))
    )
    (net (code "134") (name "TC{slash}TXRX{slash}MOSI") (class "Default")
      (node (ref "IC5") (pin "16") (pinfunction "B4_16") (pintype "bidirectional"))
      (node (ref "IC6") (pin "16") (pinfunction "B4_16") (pintype "bidirectional"))
      (node (ref "IC9") (pin "29") (pinfunction "PF1_29") (pintype "bidirectional"))
    )
    (net (code "135") (name "TC{slash}TXRX{slash}RST") (class "Default")
      (node (ref "IC5") (pin "12") (pinfunction "B8_12") (pintype "bidirectional"))
      (node (ref "IC6") (pin "17") (pinfunction "B3_17") (pintype "bidirectional"))
      (node (ref "IC9") (pin "1") (pinfunction "PB6_1") (pintype "bidirectional"))
    )
    (net (code "136") (name "TC{slash}TX{slash}CS") (class "Default")
      (node (ref "IC6") (pin "13") (pinfunction "B7_13") (pintype "bidirectional"))
      (node (ref "IC9") (pin "31") (pinfunction "PF3_31") (pintype "bidirectional"))
    )
    (net (code "137") (name "TMP{slash}SCL") (class "Default")
      (node (ref "IC14") (pin "1") (pinfunction "SCL_1") (pintype "passive"))
      (node (ref "IC16") (pin "2") (pinfunction "SCL_2") (pintype "input"))
      (node (ref "IC18") (pin "2") (pinfunction "SCL_2") (pintype "input"))
      (node (ref "IC9") (pin "47") (pinfunction "PB2/I2C0SCL_47") (pintype "bidirectional"))
      (node (ref "R24") (pin "1") (pinfunction "P$1_1") (pintype "passive"))
      (node (ref "TP10") (pin "TP") (pinfunction "TP_TP") (pintype "input"))
    )
    (net (code "138") (name "TMP{slash}SDA") (class "Default")
      (node (ref "IC14") (pin "6") (pinfunction "SDA_6") (pintype "passive"))
      (node (ref "IC16") (pin "1") (pinfunction "SDA_1") (pintype "open_collector"))
      (node (ref "IC18") (pin "1") (pinfunction "SDA_1") (pintype "open_collector"))
      (node (ref "IC9") (pin "48") (pinfunction "PB3/I2C0SDA_48") (pintype "bidirectional"))
      (node (ref "R23") (pin "1") (pinfunction "P$1_1") (pintype "passive"))
      (node (ref "TP9") (pin "TP") (pinfunction "TP_TP") (pintype "input"))
    )
    (net (code "139") (name "TX_CLK") (class "Default")
      (node (ref "IC6") (pin "7") (pinfunction "A6_7") (pintype "bidirectional"))
      (node (ref "IC7") (pin "8") (pinfunction "SCK_8") (pintype "bidirectional"))
      (node (ref "TP8") (pin "TP") (pinfunction "TP_TP") (pintype "input"))
    )
    (net (code "140") (name "TX_CS") (class "Default")
      (node (ref "IC3") (pin "1") (pinfunction "P1.1_1") (pintype "bidirectional"))
      (node (ref "IC6") (pin "8") (pinfunction "A7_8") (pintype "bidirectional"))
      (node (ref "IC7") (pin "11") (pinfunction "CSN_11") (pintype "bidirectional"))
      (node (ref "TP7") (pin "TP") (pinfunction "TP_TP") (pintype "input"))
    )
    (net (code "141") (name "TX_GPIO0") (class "Default")
      (node (ref "IC3") (pin "15") (pinfunction "P1.3_15") (pintype "bidirectional"))
      (node (ref "IC6") (pin "1") (pinfunction "A1_1") (pintype "bidirectional"))
      (node (ref "IC7") (pin "10") (pinfunction "GPIO0_10") (pintype "bidirectional"))
      (node (ref "TP13") (pin "TP") (pinfunction "TP_TP") (pintype "input"))
    )
    (net (code "142") (name "TX_GPIO2") (class "Default")
      (node (ref "IC7") (pin "4") (pinfunction "GPIO2_4") (pintype "bidirectional"))
    )
    (net (code "143") (name "TX_GPIO3") (class "Default")
      (node (ref "IC7") (pin "3") (pinfunction "GPIO3_3") (pintype "bidirectional"))
      (node (ref "IC77") (pin "1") (pinfunction "A_1") (pintype "input"))
      (node (ref "LED6") (pin "A") (pinfunction "A_A") (pintype "passive"))
      (node (ref "TP15") (pin "TP") (pinfunction "TP_TP") (pintype "input"))
    )
    (net (code "144") (name "TX_MISO") (class "Default")
      (node (ref "IC6") (pin "6") (pinfunction "A5_6") (pintype "bidirectional"))
      (node (ref "IC7") (pin "9") (pinfunction "MISO_9") (pintype "bidirectional"))
      (node (ref "TP12") (pin "TP") (pinfunction "TP_TP") (pintype "input"))
    )
    (net (code "145") (name "TX_MOSI") (class "Default")
      (node (ref "IC6") (pin "5") (pinfunction "A4_5") (pintype "bidirectional"))
      (node (ref "IC7") (pin "7") (pinfunction "MOSI_7") (pintype "bidirectional"))
      (node (ref "TP11") (pin "TP") (pinfunction "TP_TP") (pintype "input"))
    )
    (net (code "146") (name "TX_REG_EN") (class "Default")
      (node (ref "IC2") (pin "3") (pinfunction "EN_3") (pintype "input"))
      (node (ref "IC9") (pin "24") (pinfunction "PA7_24") (pintype "bidirectional"))
      (node (ref "R4") (pin "1") (pinfunction "P$1_1") (pintype "passive"))
    )
    (net (code "147") (name "TX_RST") (class "Default")
      (node (ref "IC3") (pin "16") (pinfunction "P1.2_16") (pintype "bidirectional"))
      (node (ref "IC6") (pin "4") (pinfunction "A3_4") (pintype "bidirectional"))
      (node (ref "IC7") (pin "2") (pinfunction "NRESET_2") (pintype "bidirectional"))
      (node (ref "R7") (pin "1") (pinfunction "P$1_1") (pintype "passive"))
      (node (ref "TP6") (pin "TP") (pinfunction "TP_TP") (pintype "input"))
    )
    (net (code "148") (name "TX{slash}GPIO0") (class "Default")
      (node (ref "IC6") (pin "20") (pinfunction "B1_20") (pintype "bidirectional"))
      (node (ref "IC9") (pin "19") (pinfunction "PA2/SSI0CLK_19") (pintype "bidirectional"))
    )
    (net (code "149") (name "TX{slash}WDT{slash}ACK") (class "Default")
      (node (ref "IC6") (pin "18") (pinfunction "B2_18") (pintype "bidirectional"))
      (node (ref "IC9") (pin "21") (pinfunction "PA4/SSI0RX_21") (pintype "bidirectional"))
    )
    (net (code "150") (name "TX{slash}WDT{slash}ERR") (class "Default")
      (node (ref "IC6") (pin "12") (pinfunction "B8_12") (pintype "bidirectional"))
      (node (ref "IC9") (pin "22") (pinfunction "PA5/SSI0TX_22") (pintype "bidirectional"))
    )
    (net (code "151") (name "WDT_ACK") (class "Default")
      (node (ref "IC3") (pin "13") (pinfunction "P1.5_13") (pintype "bidirectional"))
      (node (ref "IC6") (pin "3") (pinfunction "A2_3") (pintype "bidirectional"))
    )
    (net (code "152") (name "WDT_ERR") (class "Default")
      (node (ref "IC3") (pin "14") (pinfunction "P1.4_14") (pintype "bidirectional"))
      (node (ref "IC6") (pin "9") (pinfunction "A8_9") (pintype "bidirectional"))
    )
    (net (code "153") (name "WDT_PA_EN") (class "Default")
      (node (ref "IC3") (pin "2") (pinfunction "P1.0_2") (pintype "bidirectional"))
      (node (ref "IC77") (pin "2") (pinfunction "B_2") (pintype "input"))
      (node (ref "LED5") (pin "A") (pinfunction "A_A") (pintype "passive"))
      (node (ref "TP14") (pin "TP") (pinfunction "TP_TP") (pintype "input"))
    )
    (net (code "154") (name "WDT{slash}KICK") (class "Default")
      (node (ref "IC13") (pin "1") (pinfunction "WDI_1") (pintype "input"))
      (node (ref "IC9") (pin "5") (pinfunction "PF4_5") (pintype "bidirectional"))
    )
    (net (code "155") (name "unconnected-(IC3-P2.6-Pad8)") (class "Default")
      (node (ref "IC3") (pin "8") (pinfunction "P2.6_8") (pintype "bidirectional"))
    )
    (net (code "156") (name "unconnected-(IC3-P2.7-Pad7)") (class "Default")
      (node (ref "IC3") (pin "7") (pinfunction "P2.7_7") (pintype "bidirectional"))
    )
    (net (code "157") (name "unconnected-(IC3-TRI0--Pad12)") (class "Default")
      (node (ref "IC3") (pin "12") (pinfunction "TRI0-_12") (pintype "bidirectional"))
    )
    (net (code "158") (name "unconnected-(IC5-A2-Pad3)") (class "Default")
      (node (ref "IC5") (pin "3") (pinfunction "A2_3") (pintype "bidirectional"))
    )
    (net (code "159") (name "unconnected-(IC5-A3-Pad4)") (class "Default")
      (node (ref "IC5") (pin "4") (pinfunction "A3_4") (pintype "bidirectional"))
    )
    (net (code "160") (name "unconnected-(IC5-B2-Pad18)") (class "Default")
      (node (ref "IC5") (pin "18") (pinfunction "B2_18") (pintype "bidirectional"))
    )
    (net (code "161") (name "unconnected-(IC5-B3-Pad17)") (class "Default")
      (node (ref "IC5") (pin "17") (pinfunction "B3_17") (pintype "bidirectional"))
    )
    (net (code "162") (name "unconnected-(IC7-NC-Pad16)") (class "Default")
      (node (ref "IC7") (pin "16") (pinfunction "NC_16") (pintype "bidirectional"))
    )
    (net (code "163") (name "unconnected-(IC7-XOSC_Q2-Pad31)") (class "Default")
      (node (ref "IC7") (pin "31") (pinfunction "XOSC_Q2_31") (pintype "bidirectional"))
    )
    (net (code "164") (name "unconnected-(IC8-NC-Pad16)") (class "Default")
      (node (ref "IC8") (pin "16") (pinfunction "NC_16") (pintype "bidirectional"))
    )
    (net (code "165") (name "unconnected-(IC8-PA-Pad17)") (class "Default")
      (node (ref "IC8") (pin "17") (pinfunction "PA_17") (pintype "bidirectional"))
    )
    (net (code "166") (name "unconnected-(IC8-TRX_SW-Pad18)") (class "Default")
      (node (ref "IC8") (pin "18") (pinfunction "TRX_SW_18") (pintype "bidirectional"))
    )
    (net (code "167") (name "unconnected-(IC8-XOSC_Q2-Pad31)") (class "Default")
      (node (ref "IC8") (pin "31") (pinfunction "XOSC_Q2_31") (pintype "bidirectional"))
    )
    (net (code "168") (name "unconnected-(IC9-PD1-Pad62)") (class "Default")
      (node (ref "IC9") (pin "62") (pinfunction "PD1_62") (pintype "bidirectional"))
    )
    (net (code "169") (name "unconnected-(IC9-PD2-Pad63)") (class "Default")
      (node (ref "IC9") (pin "63") (pinfunction "PD2_63") (pintype "bidirectional"))
    )
    (net (code "170") (name "unconnected-(IC9-PD3-Pad64)") (class "Default")
      (node (ref "IC9") (pin "64") (pinfunction "PD3_64") (pintype "bidirectional"))
    )
    (net (code "171") (name "unconnected-(IC9-PD6-Pad53)") (class "Default")
      (node (ref "IC9") (pin "53") (pinfunction "PD6_53") (pintype "bidirectional"))
    )
    (net (code "172") (name "unconnected-(IC9-~{HIB}-Pad33)") (class "Default")
      (node (ref "IC9") (pin "33") (pinfunction "~{HIB}_33") (pintype "bidirectional"))
    )
    (net (code "173") (name "unconnected-(IC11-AUX_CL-Pad7)") (class "Default")
      (node (ref "IC11") (pin "7") (pinfunction "AUX_CL_7") (pintype "bidirectional"))
    )
    (net (code "174") (name "unconnected-(IC11-AUX_DA-Pad21)") (class "Default")
      (node (ref "IC11") (pin "21") (pinfunction "AUX_DA_21") (pintype "bidirectional"))
    )
    (net (code "175") (name "unconnected-(IC11-INT-Pad12)") (class "Default")
      (node (ref "IC11") (pin "12") (pinfunction "INT_12") (pintype "bidirectional"))
    )
    (net (code "176") (name "unconnected-(IC12-B1-Pad20)") (class "Default")
      (node (ref "IC12") (pin "20") (pinfunction "B1_20") (pintype "bidirectional"))
    )
    (net (code "177") (name "unconnected-(IC12-B2-Pad18)") (class "Default")
      (node (ref "IC12") (pin "18") (pinfunction "B2_18") (pintype "bidirectional"))
    )
    (net (code "178") (name "unconnected-(IC12-B5-Pad15)") (class "Default")
      (node (ref "IC12") (pin "15") (pinfunction "B5_15") (pintype "bidirectional"))
    )
    (net (code "179") (name "unconnected-(IC12-B6-Pad14)") (class "Default")
      (node (ref "IC12") (pin "14") (pinfunction "B6_14") (pintype "bidirectional"))
    )
    (net (code "180") (name "unconnected-(IC12-B7-Pad13)") (class "Default")
      (node (ref "IC12") (pin "13") (pinfunction "B7_13") (pintype "bidirectional"))
    )
    (net (code "181") (name "unconnected-(IC12-B8-Pad12)") (class "Default")
      (node (ref "IC12") (pin "12") (pinfunction "B8_12") (pintype "bidirectional"))
    )
    (net (code "182") (name "unconnected-(IC16-OS-Pad3)") (class "Default")
      (node (ref "IC16") (pin "3") (pinfunction "OS_3") (pintype "open_collector"))
    )
    (net (code "183") (name "unconnected-(IC18-OS-Pad3)") (class "Default")
      (node (ref "IC18") (pin "3") (pinfunction "OS_3") (pintype "open_collector"))
    )
    (net (code "184") (name "unconnected-(J3-KEY-Pad7)") (class "Default")
      (node (ref "J3") (pin "7") (pinfunction "KEY_7") (pintype "bidirectional"))
    )
    (net (code "185") (name "unconnected-(J3-NC-Pad8)") (class "Default")
      (node (ref "J3") (pin "8") (pinfunction "NC_8") (pintype "no_connect"))
    )
    (net (code "186") (name "unconnected-(SV2-Pad5)") (class "Default")
      (node (ref "SV2") (pin "5") (pinfunction "5_5") (pintype "passive"))
    )
    (net (code "187") (name "unconnected-(SV2-Pad6)") (class "Default")
      (node (ref "SV2") (pin "6") (pinfunction "6_6") (pintype "passive"))
    )
    (net (code "188") (name "unconnected-(SV2-Pad7)") (class "Default")
      (node (ref "SV2") (pin "7") (pinfunction "7_7") (pintype "passive"))
    )
    (net (code "189") (name "unconnected-(SV2-Pad8)") (class "Default")
      (node (ref "SV2") (pin "8") (pinfunction "8_8") (pintype "passive"))
    )
    (net (code "190") (name "unconnected-(SV2-Pad9)") (class "Default")
      (node (ref "SV2") (pin "9") (pinfunction "9_9") (pintype "passive"))
    )
    (net (code "191") (name "unconnected-(SV2-Pad11)") (class "Default")
      (node (ref "SV2") (pin "11") (pinfunction "11_11") (pintype "passive"))
    )
    (net (code "192") (name "unconnected-(SV2-Pad12)") (class "Default")
      (node (ref "SV2") (pin "12") (pinfunction "12_12") (pintype "passive"))
    )
    (net (code "193") (name "unconnected-(SV2-Pad13)") (class "Default")
      (node (ref "SV2") (pin "13") (pinfunction "13_13") (pintype "passive"))
    )
    (net (code "194") (name "unconnected-(SV2-Pad14)") (class "Default")
      (node (ref "SV2") (pin "14") (pinfunction "14_14") (pintype "passive"))
    )
    (net (code "195") (name "unconnected-(SV2-Pad17)") (class "Default")
      (node (ref "SV2") (pin "17") (pinfunction "17_17") (pintype "passive"))
    )
    (net (code "196") (name "unconnected-(SV2-Pad18)") (class "Default")
      (node (ref "SV2") (pin "18") (pinfunction "18_18") (pintype "passive"))
    )
    (net (code "197") (name "unconnected-(SV2-Pad19)") (class "Default")
      (node (ref "SV2") (pin "19") (pinfunction "19_19") (pintype "passive"))
    )
    (net (code "198") (name "unconnected-(SV2-Pad20)") (class "Default")
      (node (ref "SV2") (pin "20") (pinfunction "20_20") (pintype "passive"))
    )
    (net (code "199") (name "unconnected-(SV2-Pad21)") (class "Default")
      (node (ref "SV2") (pin "21") (pinfunction "21_21") (pintype "passive"))
    )
    (net (code "200") (name "unconnected-(SV2-Pad23)") (class "Default")
      (node (ref "SV2") (pin "23") (pinfunction "23_23") (pintype "passive"))
    )
    (net (code "201") (name "unconnected-(SV2-Pad24)") (class "Default")
      (node (ref "SV2") (pin "24") (pinfunction "24_24") (pintype "passive"))
    )
    (net (code "202") (name "unconnected-(SV2-Pad25)") (class "Default")
      (node (ref "SV2") (pin "25") (pinfunction "25_25") (pintype "passive"))
    )
    (net (code "203") (name "unconnected-(SV2-Pad26)") (class "Default")
      (node (ref "SV2") (pin "26") (pinfunction "26_26") (pintype "passive"))
    )
    (net (code "204") (name "unconnected-(SV2-Pad27)") (class "Default")
      (node (ref "SV2") (pin "27") (pinfunction "27_27") (pintype "passive"))
    )
    (net (code "205") (name "unconnected-(SV2-Pad28)") (class "Default")
      (node (ref "SV2") (pin "28") (pinfunction "28_28") (pintype "passive"))
    )
    (net (code "206") (name "unconnected-(SV2-Pad29)") (class "Default")
      (node (ref "SV2") (pin "29") (pinfunction "29_29") (pintype "passive"))
    )
    (net (code "207") (name "unconnected-(SV2-Pad30)") (class "Default")
      (node (ref "SV2") (pin "30") (pinfunction "30_30") (pintype "passive"))
    )
    (net (code "208") (name "unconnected-(SV2-Pad31)") (class "Default")
      (node (ref "SV2") (pin "31") (pinfunction "31_31") (pintype "passive"))
    )
    (net (code "209") (name "unconnected-(SV2-Pad32)") (class "Default")
      (node (ref "SV2") (pin "32") (pinfunction "32_32") (pintype "passive"))
    )
    (net (code "210") (name "unconnected-(SV2-Pad33)") (class "Default")
      (node (ref "SV2") (pin "33") (pinfunction "33_33") (pintype "passive"))
    )
    (net (code "211") (name "unconnected-(SV2-Pad34)") (class "Default")
      (node (ref "SV2") (pin "34") (pinfunction "34_34") (pintype "passive"))
    )
    (net (code "212") (name "unconnected-(SV2-Pad35)") (class "Default")
      (node (ref "SV2") (pin "35") (pinfunction "35_35") (pintype "passive"))
    )
    (net (code "213") (name "unconnected-(SV2-Pad36)") (class "Default")
      (node (ref "SV2") (pin "36") (pinfunction "36_36") (pintype "passive"))
    )
    (net (code "214") (name "unconnected-(SV2-Pad37)") (class "Default")
      (node (ref "SV2") (pin "37") (pinfunction "37_37") (pintype "passive"))
    )
    (net (code "215") (name "unconnected-(SV2-Pad38)") (class "Default")
      (node (ref "SV2") (pin "38") (pinfunction "38_38") (pintype "passive"))
    )
    (net (code "216") (name "unconnected-(SV2-Pad39)") (class "Default")
      (node (ref "SV2") (pin "39") (pinfunction "39_39") (pintype "passive"))
    )
    (net (code "217") (name "unconnected-(SV2-Pad40)") (class "Default")
      (node (ref "SV2") (pin "40") (pinfunction "40_40") (pintype "passive"))
    )
    (net (code "218") (name "unconnected-(SV2-Pad41)") (class "Default")
      (node (ref "SV2") (pin "41") (pinfunction "41_41") (pintype "passive"))
    )
    (net (code "219") (name "unconnected-(SV2-Pad42)") (class "Default")
      (node (ref "SV2") (pin "42") (pinfunction "42_42") (pintype "passive"))
    )
    (net (code "220") (name "unconnected-(SV2-Pad43)") (class "Default")
      (node (ref "SV2") (pin "43") (pinfunction "43_43") (pintype "passive"))
    )
    (net (code "221") (name "unconnected-(SV2-Pad44)") (class "Default")
      (node (ref "SV2") (pin "44") (pinfunction "44_44") (pintype "passive"))
    )
    (net (code "222") (name "unconnected-(SV2-Pad45)") (class "Default")
      (node (ref "SV2") (pin "45") (pinfunction "45_45") (pintype "passive"))
    )
    (net (code "223") (name "unconnected-(SV2-Pad46)") (class "Default")
      (node (ref "SV2") (pin "46") (pinfunction "46_46") (pintype "passive"))
    )
    (net (code "224") (name "unconnected-(SV3-Pad6)") (class "Default")
      (node (ref "SV3") (pin "6") (pinfunction "6_6") (pintype "passive"))
    )
    (net (code "225") (name "unconnected-(SV3-Pad7)") (class "Default")
      (node (ref "SV3") (pin "7") (pinfunction "7_7") (pintype "passive"))
    )
    (net (code "226") (name "unconnected-(SV3-Pad8)") (class "Default")
      (node (ref "SV3") (pin "8") (pinfunction "8_8") (pintype "passive"))
    )
    (net (code "227") (name "unconnected-(SV3-Pad9)") (class "Default")
      (node (ref "SV3") (pin "9") (pinfunction "9_9") (pintype "passive"))
    )
    (net (code "228") (name "unconnected-(SV3-Pad10)") (class "Default")
      (node (ref "SV3") (pin "10") (pinfunction "10_10") (pintype "passive"))
    )
    (net (code "229") (name "unconnected-(SV3-Pad11)") (class "Default")
      (node (ref "SV3") (pin "11") (pinfunction "11_11") (pintype "passive"))
    )
    (net (code "230") (name "unconnected-(SV3-Pad12)") (class "Default")
      (node (ref "SV3") (pin "12") (pinfunction "12_12") (pintype "passive"))
    )
    (net (code "231") (name "unconnected-(SV3-Pad13)") (class "Default")
      (node (ref "SV3") (pin "13") (pinfunction "13_13") (pintype "passive"))
    )
    (net (code "232") (name "unconnected-(SV3-Pad14)") (class "Default")
      (node (ref "SV3") (pin "14") (pinfunction "14_14") (pintype "passive"))
    )
    (net (code "233") (name "unconnected-(SV3-Pad15)") (class "Default")
      (node (ref "SV3") (pin "15") (pinfunction "15_15") (pintype "passive"))
    )
    (net (code "234") (name "unconnected-(SV3-Pad16)") (class "Default")
      (node (ref "SV3") (pin "16") (pinfunction "16_16") (pintype "passive"))
    )
    (net (code "235") (name "unconnected-(SV3-Pad17)") (class "Default")
      (node (ref "SV3") (pin "17") (pinfunction "17_17") (pintype "passive"))
    )
    (net (code "236") (name "unconnected-(SV3-Pad18)") (class "Default")
      (node (ref "SV3") (pin "18") (pinfunction "18_18") (pintype "passive"))
    )
    (net (code "237") (name "unconnected-(SV3-Pad20)") (class "Default")
      (node (ref "SV3") (pin "20") (pinfunction "20_20") (pintype "passive"))
    )
    (net (code "238") (name "unconnected-(SV3-Pad22)") (class "Default")
      (node (ref "SV3") (pin "22") (pinfunction "22_22") (pintype "passive"))
    )
    (net (code "239") (name "unconnected-(SV3-Pad23)") (class "Default")
      (node (ref "SV3") (pin "23") (pinfunction "23_23") (pintype "passive"))
    )
    (net (code "240") (name "unconnected-(SV3-Pad24)") (class "Default")
      (node (ref "SV3") (pin "24") (pinfunction "24_24") (pintype "passive"))
    )
    (net (code "241") (name "unconnected-(SV3-Pad33)") (class "Default")
      (node (ref "SV3") (pin "33") (pinfunction "33_33") (pintype "passive"))
    )
    (net (code "242") (name "unconnected-(SV3-Pad34)") (class "Default")
      (node (ref "SV3") (pin "34") (pinfunction "34_34") (pintype "passive"))
    )
    (net (code "243") (name "unconnected-(SV3-Pad35)") (class "Default")
      (node (ref "SV3") (pin "35") (pinfunction "35_35") (pintype "passive"))
    )
    (net (code "244") (name "unconnected-(SV3-Pad36)") (class "Default")
      (node (ref "SV3") (pin "36") (pinfunction "36_36") (pintype "passive"))
    )
    (net (code "245") (name "unconnected-(SV3-Pad37)") (class "Default")
      (node (ref "SV3") (pin "37") (pinfunction "37_37") (pintype "passive"))
    )
    (net (code "246") (name "unconnected-(SV3-Pad38)") (class "Default")
      (node (ref "SV3") (pin "38") (pinfunction "38_38") (pintype "passive"))
    )
    (net (code "247") (name "unconnected-(SV3-Pad39)") (class "Default")
      (node (ref "SV3") (pin "39") (pinfunction "39_39") (pintype "passive"))
    )
    (net (code "248") (name "unconnected-(SV3-Pad40)") (class "Default")
      (node (ref "SV3") (pin "40") (pinfunction "40_40") (pintype "passive"))
    )
    (net (code "249") (name "unconnected-(SV3-Pad41)") (class "Default")
      (node (ref "SV3") (pin "41") (pinfunction "41_41") (pintype "passive"))
    )
    (net (code "250") (name "unconnected-(SV3-Pad42)") (class "Default")
      (node (ref "SV3") (pin "42") (pinfunction "42_42") (pintype "passive"))
    )
    (net (code "251") (name "unconnected-(SV3-Pad43)") (class "Default")
      (node (ref "SV3") (pin "43") (pinfunction "43_43") (pintype "passive"))
    )
    (net (code "252") (name "unconnected-(SV3-Pad44)") (class "Default")
      (node (ref "SV3") (pin "44") (pinfunction "44_44") (pintype "passive"))
    )
    (net (code "253") (name "unconnected-(SV3-Pad45)") (class "Default")
      (node (ref "SV3") (pin "45") (pinfunction "45_45") (pintype "passive"))
    )
    (net (code "254") (name "unconnected-(SV3-Pad46)") (class "Default")
      (node (ref "SV3") (pin "46") (pinfunction "46_46") (pintype "passive"))
    )
    (net (code "255") (name "unconnected-(SV3-Pad48)") (class "Default")
      (node (ref "SV3") (pin "48") (pinfunction "48_48") (pintype "passive"))
    )
    (net (code "256") (name "unconnected-(SV3-Pad49)") (class "Default")
      (node (ref "SV3") (pin "49") (pinfunction "49_49") (pintype "passive"))
    )
    (net (code "257") (name "unconnected-(SV3-Pad50)") (class "Default")
      (node (ref "SV3") (pin "50") (pinfunction "50_50") (pintype "passive"))
    )
    (net (code "258") (name "unconnected-(SV3-Pad51)") (class "Default")
      (node (ref "SV3") (pin "51") (pinfunction "51_51") (pintype "passive"))
    )
    (net (code "259") (name "unconnected-(SV3-Pad52)") (class "Default")
      (node (ref "SV3") (pin "52") (pinfunction "52_52") (pintype "passive"))
    )
    (net (code "260") (name "~{RST}") (class "Default")
      (node (ref "IC13") (pin "6") (pinfunction "*RESET_6") (pintype "output"))
      (node (ref "IC9") (pin "38") (pinfunction "~{RST}_38") (pintype "bidirectional"))
      (node (ref "J3") (pin "10") (pinfunction "NRST_10") (pintype "bidirectional"))
      (node (ref "R15") (pin "1") (pinfunction "P$1_1") (pintype "passive"))
      (node (ref "SV3") (pin "4") (pinfunction "4_4") (pintype "passive"))
    )
  )
)
